# DaughterBoard.net
KiCad netlist of a schematic drawn in EAGLE
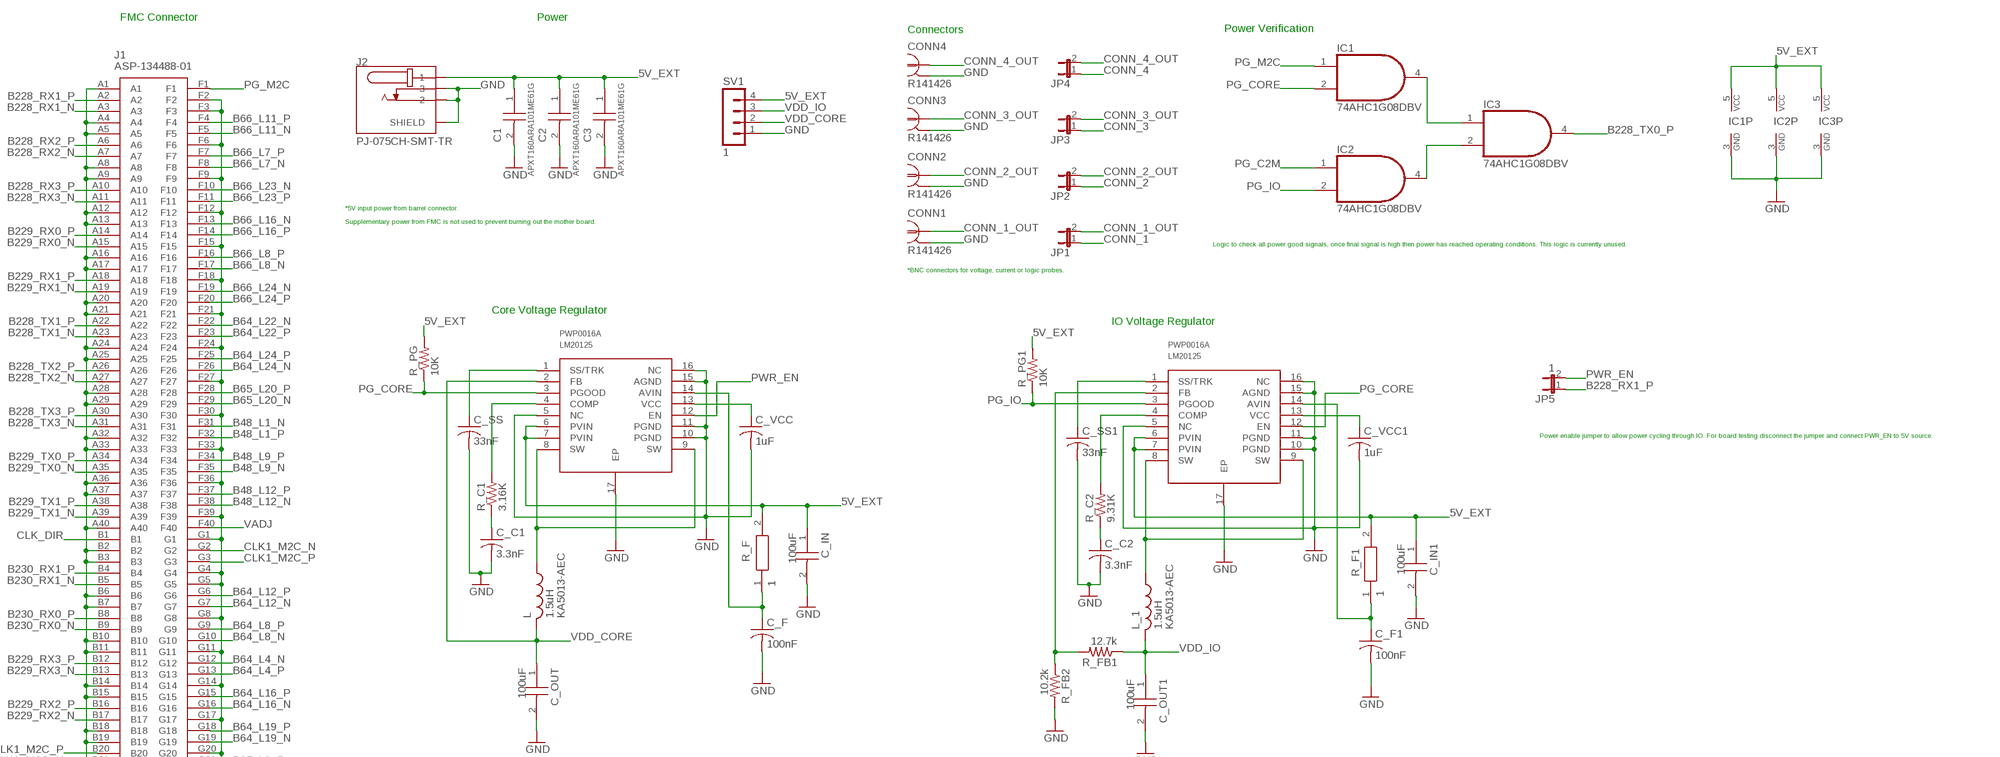
[diagram p0: schematic, sheet 1, part 1 of 3]
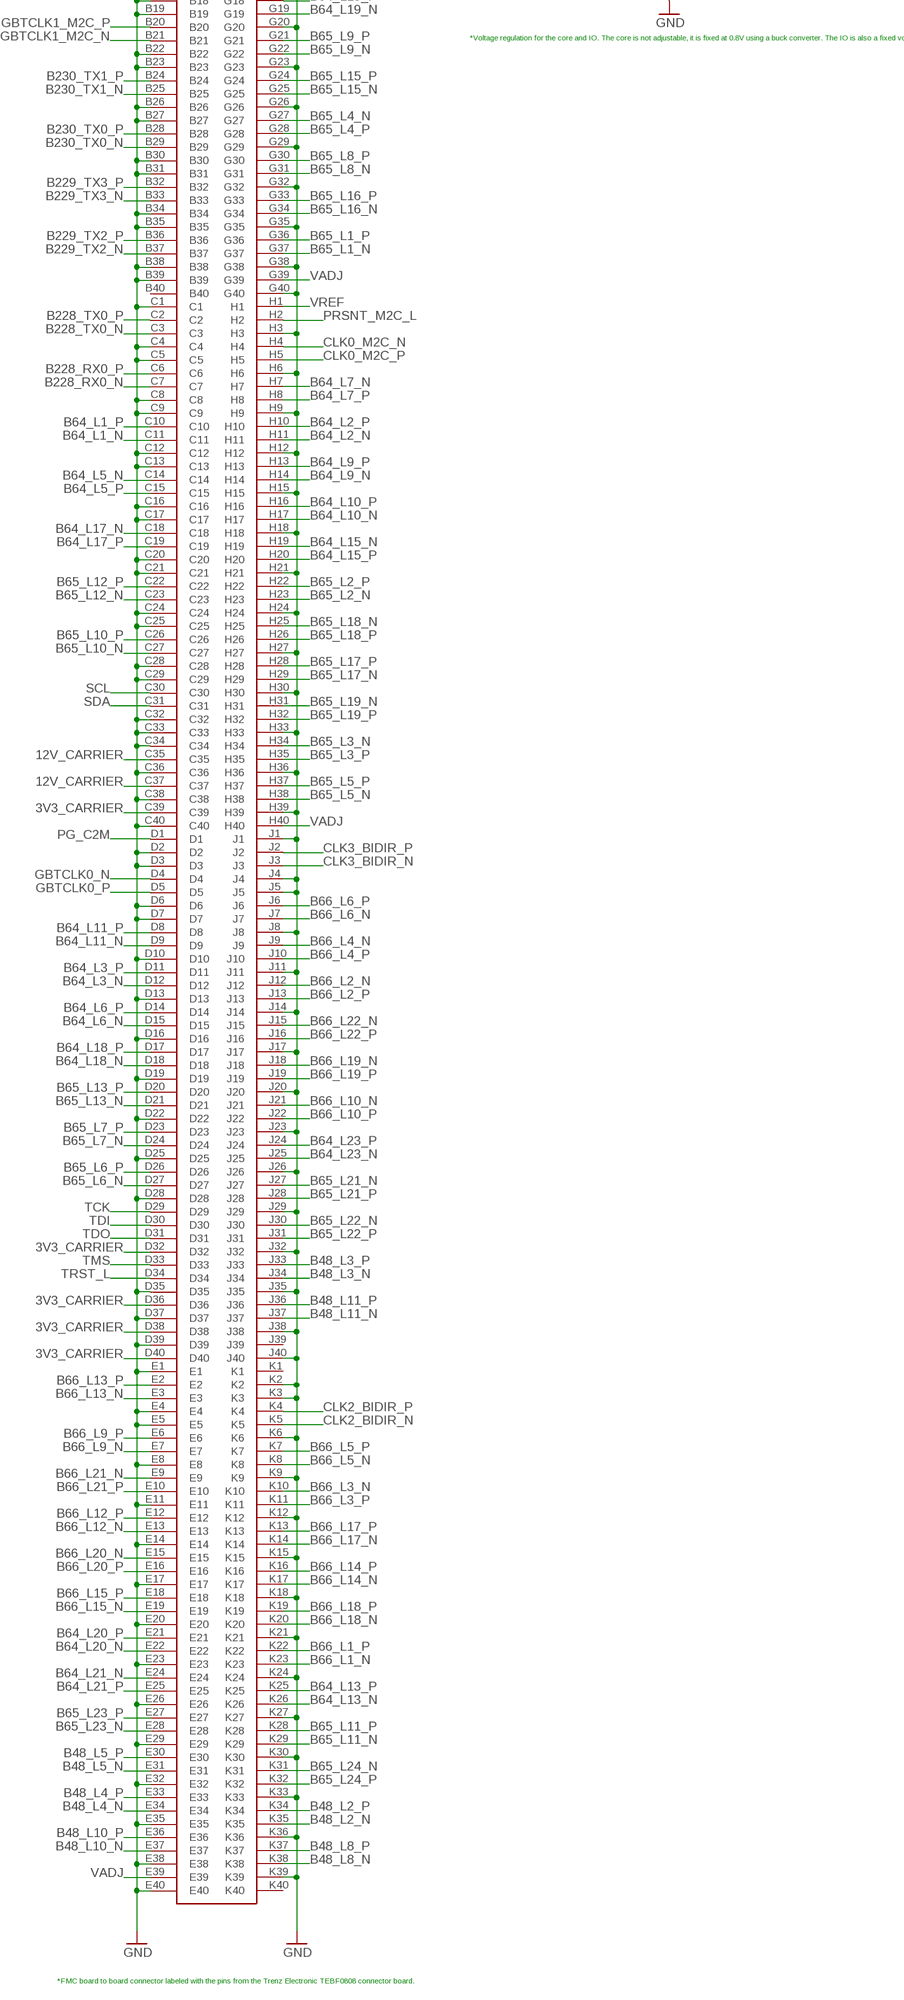
[diagram p1: schematic, sheet 1, part 2 of 3]
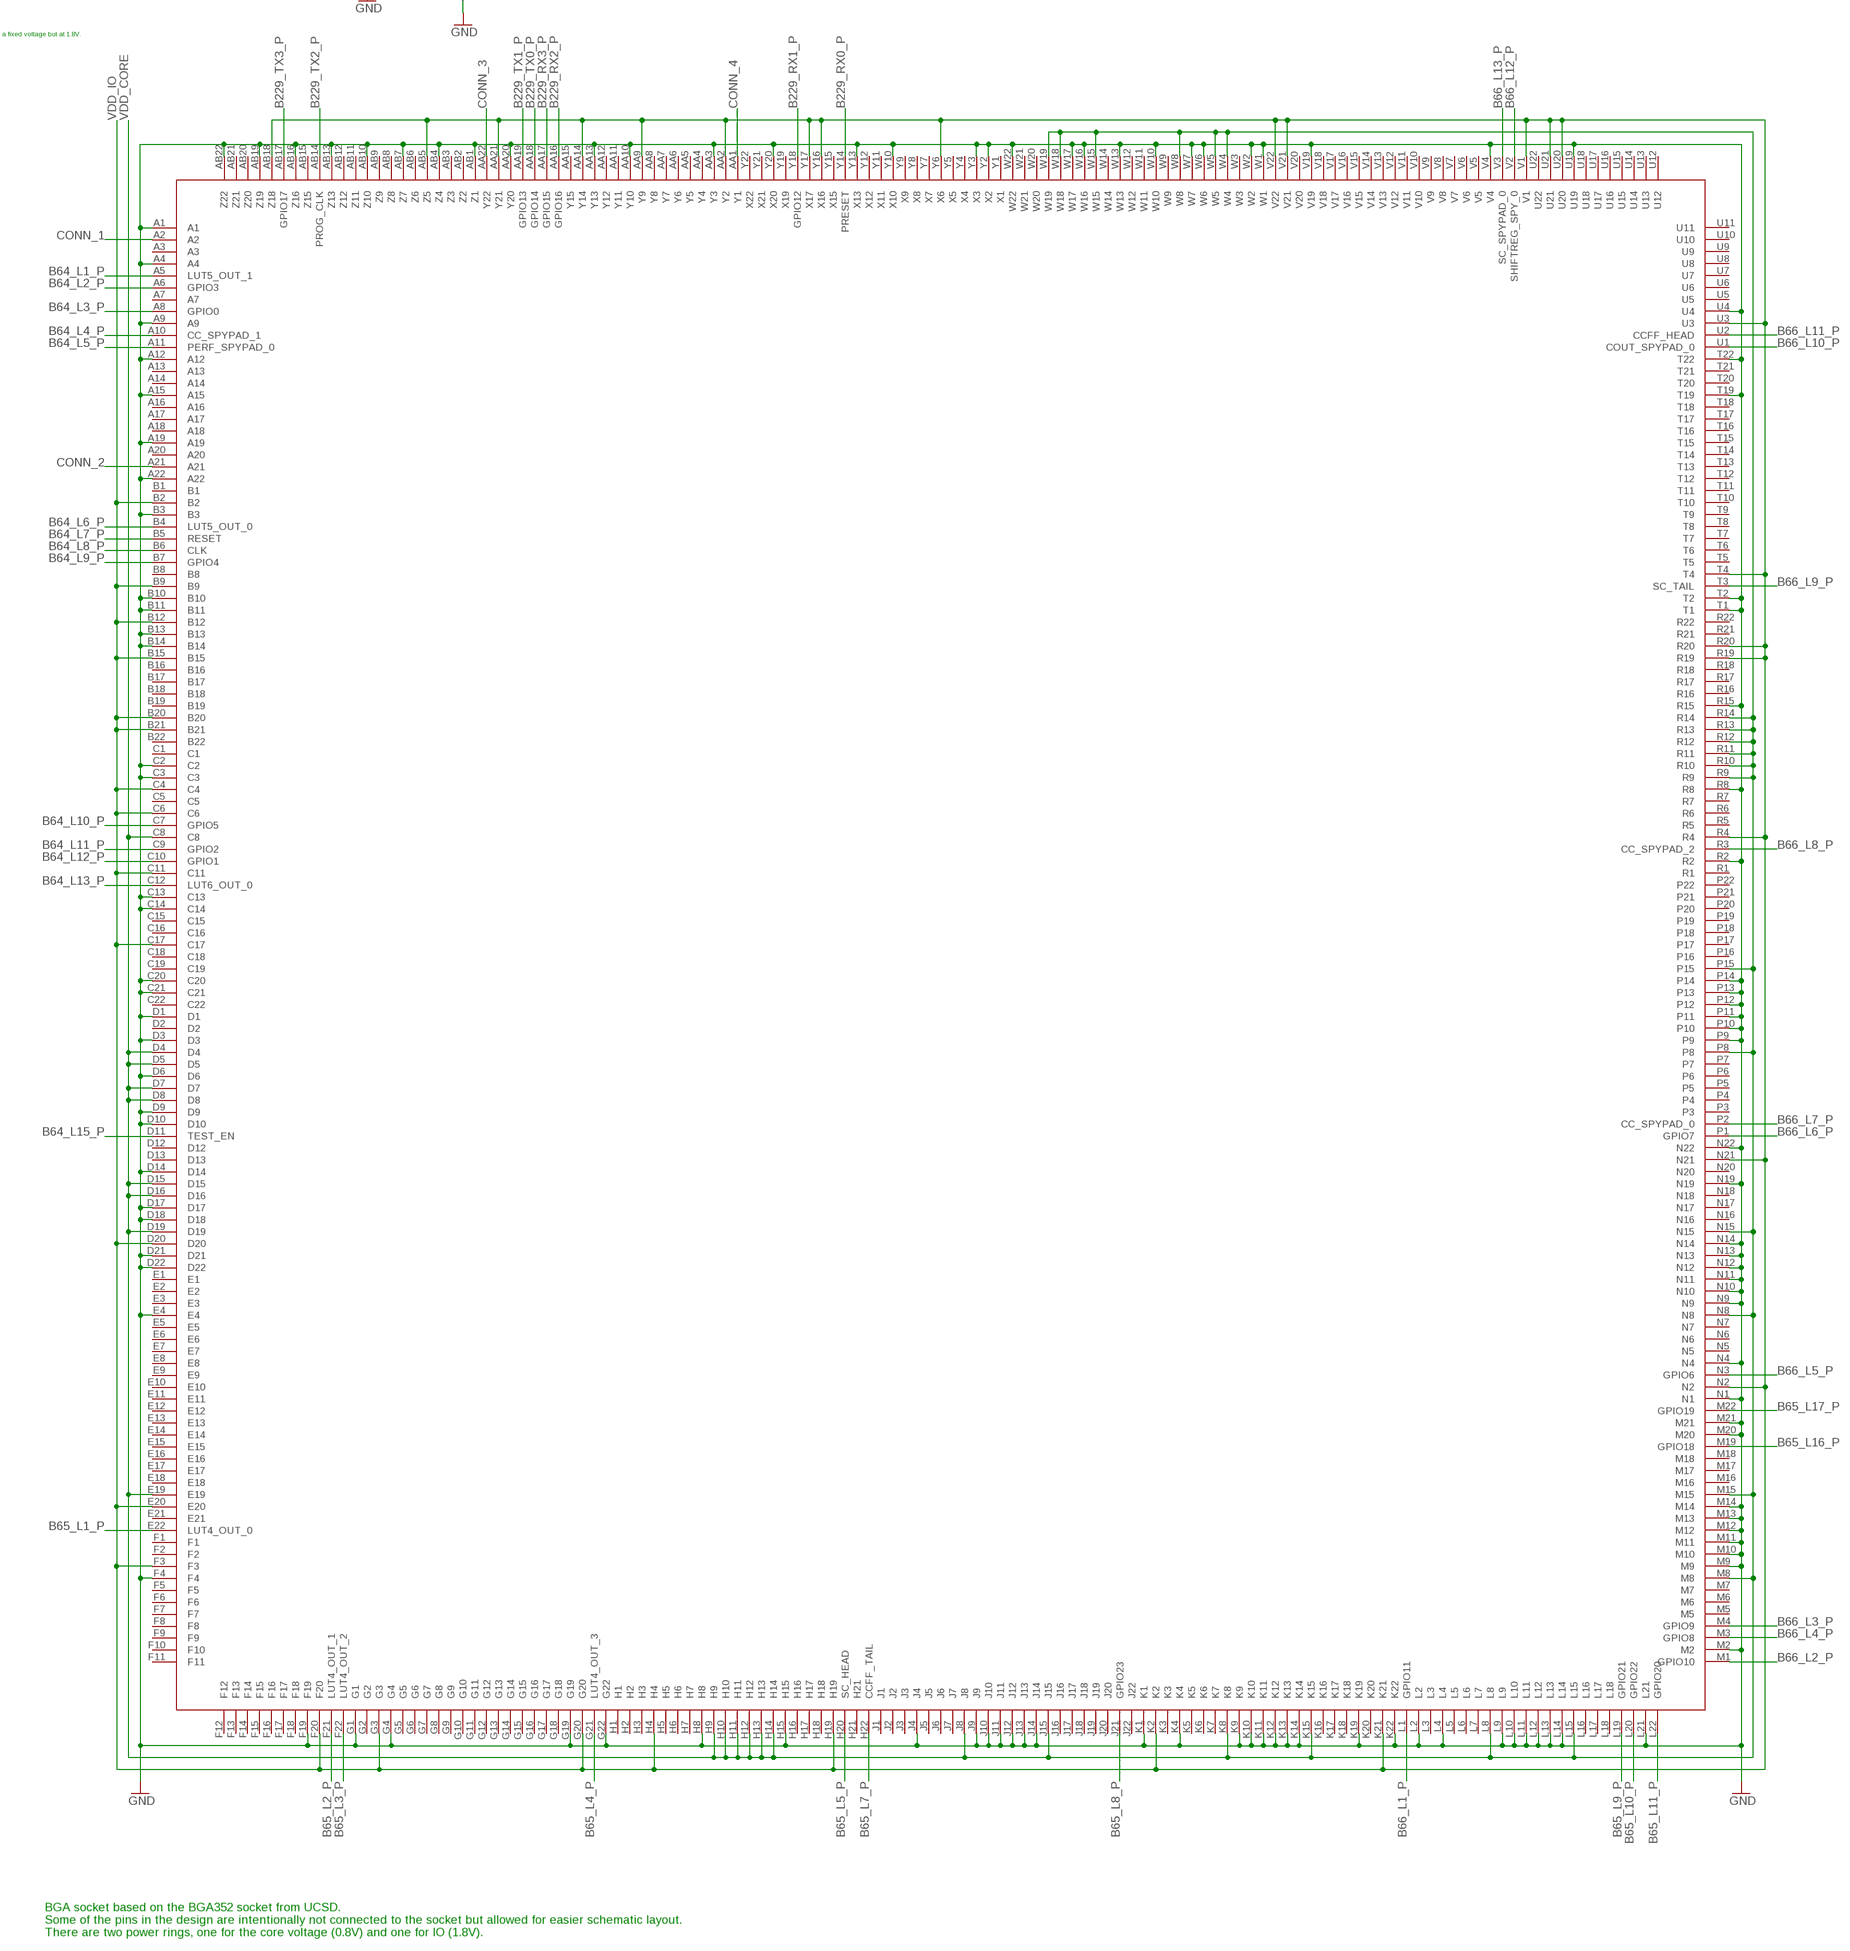
[diagram p2: schematic, sheet 1, part 3 of 3]

(export (version "E")
  (design (tool "Eeschema 10.0.6"))
  (components
    (comp (ref "C1")
      (value "APXT160ARA101ME61G")
      (footprint "eagle-import:CAPAE530X610N")
      (fields (field (name "MOUSER_PART_NUMBER") "661-APXT160A101ME61G"))
      (libsource (lib "eagle-import") (part "APXT160ARA101ME61G"))
    )
    (comp (ref "C2")
      (value "APXT160ARA101ME61G")
      (footprint "eagle-import:CAPAE530X610N")
      (fields (field (name "MOUSER_PART_NUMBER") "661-APXT160A101ME61G"))
      (libsource (lib "eagle-import") (part "APXT160ARA101ME61G"))
    )
    (comp (ref "C3")
      (value "APXT160ARA101ME61G")
      (footprint "eagle-import:CAPAE530X610N")
      (fields (field (name "MOUSER_PART_NUMBER") "661-APXT160A101ME61G"))
      (libsource (lib "eagle-import") (part "APXT160ARA101ME61G"))
    )
    (comp (ref "CONN1")
      (value "R141426")
      (footprint "eagle-import:R141426")
      (fields
        (field (name "MF") "FARNELL")
        (field (name "MPN") "R141426161")
        (field (name "SPICEPREFIX") "X")
      )
      (libsource (lib "eagle-import") (part "R141426"))
    )
    (comp (ref "CONN2")
      (value "R141426")
      (footprint "eagle-import:R141426")
      (fields (field (name "MF") "FARNELL") (field (name "MPN") "R141426161"))
      (libsource (lib "eagle-import") (part "R141426"))
    )
    (comp (ref "CONN3")
      (value "R141426")
      (footprint "eagle-import:R141426")
      (fields (field (name "MF") "FARNELL") (field (name "MPN") "R141426161"))
      (libsource (lib "eagle-import") (part "R141426"))
    )
    (comp (ref "CONN4")
      (value "R141426")
      (footprint "eagle-import:R141426")
      (fields (field (name "MF") "FARNELL") (field (name "MPN") "R141426161"))
      (libsource (lib "eagle-import") (part "R141426"))
    )
    (comp (ref "C_C1")
      (value "3.3nF")
      (footprint "eagle-import:C0805")
      (libsource (lib "eagle-import") (part "C-USC0805"))
    )
    (comp (ref "C_C2")
      (value "3.3nF")
      (footprint "eagle-import:C0805")
      (libsource (lib "eagle-import") (part "C-USC0805"))
    )
    (comp (ref "C_F")
      (value "100nF")
      (footprint "eagle-import:C0805")
      (libsource (lib "eagle-import") (part "C-USC0805"))
    )
    (comp (ref "C_F1")
      (value "100nF")
      (footprint "eagle-import:C0805")
      (libsource (lib "eagle-import") (part "C-USC0805"))
    )
    (comp (ref "C_IN")
      (value "100uF")
      (footprint "eagle-import:CAPC2012X145N")
      (fields
        (field (name "MANUFACTURER_PART_NUMBER") "GRM21BR60J107ME15L")
        (field (name "MOUSER_PART_NUMBER") "81-GRM21BR60J107ME5L")
      )
      (libsource (lib "eagle-import") (part "GRM21BR60J107ME15L"))
    )
    (comp (ref "C_IN1")
      (value "100uF")
      (footprint "eagle-import:CAPC2012X145N")
      (fields
        (field (name "MANUFACTURER_PART_NUMBER") "GRM21BR60J107ME15L")
        (field (name "MOUSER_PART_NUMBER") "81-GRM21BR60J107ME5L")
      )
      (libsource (lib "eagle-import") (part "GRM21BR60J107ME15L"))
    )
    (comp (ref "C_OUT")
      (value "100uF")
      (footprint "eagle-import:CAPC2012X145N")
      (fields
        (field (name "MANUFACTURER_PART_NUMBER") "GRM21BR60J107ME15L")
        (field (name "MOUSER_PART_NUMBER") "81-GRM21BR60J107ME5L")
      )
      (libsource (lib "eagle-import") (part "GRM21BR60J107ME15L"))
    )
    (comp (ref "C_OUT1")
      (value "100uF")
      (footprint "eagle-import:CAPC2012X145N")
      (fields
        (field (name "MANUFACTURER_PART_NUMBER") "GRM21BR60J107ME15L")
        (field (name "MOUSER_PART_NUMBER") "81-GRM21BR60J107ME5L")
      )
      (libsource (lib "eagle-import") (part "GRM21BR60J107ME15L"))
    )
    (comp (ref "C_SS")
      (value "33nF")
      (footprint "eagle-import:C0805")
      (libsource (lib "eagle-import") (part "C-USC0805"))
    )
    (comp (ref "C_SS1")
      (value "33nF")
      (footprint "eagle-import:C0805")
      (libsource (lib "eagle-import") (part "C-USC0805"))
    )
    (comp (ref "C_VCC")
      (value "1uF")
      (footprint "eagle-import:C0805")
      (libsource (lib "eagle-import") (part "C-USC0805"))
    )
    (comp (ref "C_VCC1")
      (value "1uF")
      (footprint "eagle-import:C0805")
      (libsource (lib "eagle-import") (part "C-USC0805"))
    )
    (comp (ref "IC1")
      (value "74AHC1G08DBV")
      (footprint "eagle-import:SOT23-5")
      (libsource (lib "eagle-import") (part "741G08DBVAHC"))
    )
    (comp (ref "IC2")
      (value "74AHC1G08DBV")
      (footprint "eagle-import:SOT23-5")
      (libsource (lib "eagle-import") (part "741G08DBVAHC"))
    )
    (comp (ref "IC3")
      (value "74AHC1G08DBV")
      (footprint "eagle-import:SOT23-5")
      (libsource (lib "eagle-import") (part "741G08DBVAHC"))
    )
    (comp (ref "J1")
      (value "ASP-134488-01")
      (footprint "eagle-import:ASP13448801")
      (fields (field (name "MOUSER_PART_NUMBER") "200-ASP-134488-01"))
      (libsource (lib "eagle-import") (part "ASP-134488-01"))
    )
    (comp (ref "J2")
      (value "PJ-075CH-SMT-TR")
      (footprint "eagle-import:CUI_PJ-075CH-SMT-TR")
      (fields (field (name "MANUFACTURER") "CUI"))
      (libsource (lib "eagle-import") (part "PJ-075CH-SMT-TR"))
    )
    (comp (ref "JP1")
      (value "JP1E")
      (footprint "eagle-import:JP1")
      (libsource (lib "eagle-import") (part "JP1E"))
    )
    (comp (ref "JP2")
      (value "JP1E")
      (footprint "eagle-import:JP1")
      (libsource (lib "eagle-import") (part "JP1E"))
    )
    (comp (ref "JP3")
      (value "JP1E")
      (footprint "eagle-import:JP1")
      (libsource (lib "eagle-import") (part "JP1E"))
    )
    (comp (ref "JP4")
      (value "JP1E")
      (footprint "eagle-import:JP1")
      (libsource (lib "eagle-import") (part "JP1E"))
    )
    (comp (ref "JP5")
      (value "1")
      (footprint "eagle-import:JP1")
      (libsource (lib "eagle-import") (part "JP1E"))
    )
    (comp (ref "L")
      (value "KA5013-AEC")
      (footprint "eagle-import:INDDFN400X400X180-2N")
      (libsource (lib "eagle-import") (part "KA5013-AEC"))
    )
    (comp (ref "L_1")
      (value "KA5013-AEC")
      (footprint "eagle-import:INDDFN400X400X180-2N")
      (libsource (lib "eagle-import") (part "KA5013-AEC"))
    )
    (comp (ref "R_C1")
      (value "3.16K")
      (footprint "eagle-import:R0805")
      (libsource (lib "eagle-import") (part "R-US_R0805"))
    )
    (comp (ref "R_C2")
      (value "9.31K")
      (footprint "eagle-import:R0805")
      (libsource (lib "eagle-import") (part "R-US_R0805"))
    )
    (comp (ref "R_F")
      (value "1")
      (footprint "eagle-import:RESC1608X55N")
      (fields
        (field (name "MANUFACTURER_PART_NUMBER") "RT0603BRD071RL")
        (field (name "MOUSER_PART_NUMBER") "603-RT0603BRD071RL")
      )
      (libsource (lib "eagle-import") (part "RT0603BRD071RL"))
    )
    (comp (ref "R_F1")
      (value "1")
      (footprint "eagle-import:RESC1608X55N")
      (fields
        (field (name "MANUFACTURER_PART_NUMBER") "RT0603BRD071RL")
        (field (name "MOUSER_PART_NUMBER") "603-RT0603BRD071RL")
      )
      (libsource (lib "eagle-import") (part "RT0603BRD071RL"))
    )
    (comp (ref "R_FB1")
      (value "12.7k")
      (footprint "eagle-import:R0805")
      (libsource (lib "eagle-import") (part "R-US_R0805"))
    )
    (comp (ref "R_FB2")
      (value "10.2k")
      (footprint "eagle-import:R0805")
      (libsource (lib "eagle-import") (part "R-US_R0805"))
    )
    (comp (ref "R_PG")
      (value "10K")
      (footprint "eagle-import:R0805")
      (libsource (lib "eagle-import") (part "R-US_R0805"))
    )
    (comp (ref "R_PG1")
      (value "10K")
      (footprint "eagle-import:R0805")
      (libsource (lib "eagle-import") (part "R-US_R0805"))
    )
    (comp (ref "SV1")
      (value "1")
      (footprint "eagle-import:MA04-1")
      (libsource (lib "eagle-import") (part "MA04-1"))
    )
    (comp (ref "U$1")
      (value "LM20125/LM20125Q")
      (footprint "eagle-import:SOP65P640X120-17T330L")
      (libsource (lib "eagle-import") (part "LM20125/LM20125Q"))
    )
    (comp (ref "U$2")
      (value "BGA352")
      (footprint "eagle-import:BGA484C100P22X22_2400X2400X220N")
      (libsource (lib "eagle-import") (part "BGA352"))
    )
    (comp (ref "U$3")
      (value "LM20125/LM20125Q")
      (footprint "eagle-import:SOP65P640X120-17T330L")
      (libsource (lib "eagle-import") (part "LM20125/LM20125Q"))
    )
  )
  (nets
    (net (code "1") (name "/3V3_CARRIER") (class "Default")
      (node (ref "J1") (pin "C39") (pinfunction "C39_C39") (pintype "bidirectional"))
      (node (ref "J1") (pin "D32") (pinfunction "D32_D32") (pintype "bidirectional"))
      (node (ref "J1") (pin "D36") (pinfunction "D36_D36") (pintype "bidirectional"))
      (node (ref "J1") (pin "D38") (pinfunction "D38_D38") (pintype "bidirectional"))
      (node (ref "J1") (pin "D40") (pinfunction "D40_D40") (pintype "bidirectional"))
    )
    (net (code "2") (name "/5V_EXT") (class "Default")
      (node (ref "C1") (pin "1") (pinfunction "+_1") (pintype "bidirectional"))
      (node (ref "C2") (pin "1") (pinfunction "+_1") (pintype "bidirectional"))
      (node (ref "C3") (pin "1") (pinfunction "+_1") (pintype "bidirectional"))
      (node (ref "C_IN") (pin "1") (pinfunction "1_1") (pintype "bidirectional"))
      (node (ref "C_IN1") (pin "1") (pinfunction "1_1") (pintype "bidirectional"))
      (node (ref "IC1") (pin "5") (pinfunction "VCC_5") (pintype "power_in"))
      (node (ref "IC2") (pin "5") (pinfunction "VCC_5") (pintype "power_in"))
      (node (ref "IC3") (pin "5") (pinfunction "VCC_5") (pintype "power_in"))
      (node (ref "J2") (pin "1") (pinfunction "1_1") (pintype "passive"))
      (node (ref "R_F") (pin "2") (pinfunction "2_2") (pintype "bidirectional"))
      (node (ref "R_F1") (pin "2") (pinfunction "2_2") (pintype "bidirectional"))
      (node (ref "R_PG") (pin "2") (pinfunction "2_2") (pintype "passive"))
      (node (ref "R_PG1") (pin "2") (pinfunction "2_2") (pintype "passive"))
      (node (ref "SV1") (pin "4") (pinfunction "4_4") (pintype "passive"))
      (node (ref "U$1") (pin "6") (pinfunction "PVIN_6") (pintype "bidirectional"))
      (node (ref "U$1") (pin "7") (pinfunction "PVIN_7") (pintype "bidirectional"))
      (node (ref "U$3") (pin "6") (pinfunction "PVIN_6") (pintype "bidirectional"))
      (node (ref "U$3") (pin "7") (pinfunction "PVIN_7") (pintype "bidirectional"))
    )
    (net (code "3") (name "/12V_CARRIER") (class "Default")
      (node (ref "J1") (pin "C35") (pinfunction "C35_C35") (pintype "bidirectional"))
      (node (ref "J1") (pin "C37") (pinfunction "C37_C37") (pintype "bidirectional"))
    )
    (net (code "4") (name "/B48_L1_N") (class "Default")
      (node (ref "J1") (pin "F31") (pinfunction "F31_F31") (pintype "bidirectional"))
    )
    (net (code "5") (name "/B48_L1_P") (class "Default")
      (node (ref "J1") (pin "F32") (pinfunction "F32_F32") (pintype "bidirectional"))
    )
    (net (code "6") (name "/B48_L2_N") (class "Default")
      (node (ref "J1") (pin "K35") (pinfunction "K35_K35") (pintype "bidirectional"))
    )
    (net (code "7") (name "/B48_L2_P") (class "Default")
      (node (ref "J1") (pin "K34") (pinfunction "K34_K34") (pintype "bidirectional"))
    )
    (net (code "8") (name "/B48_L3_N") (class "Default")
      (node (ref "J1") (pin "J34") (pinfunction "J34_J34") (pintype "bidirectional"))
    )
    (net (code "9") (name "/B48_L3_P") (class "Default")
      (node (ref "J1") (pin "J33") (pinfunction "J33_J33") (pintype "bidirectional"))
    )
    (net (code "10") (name "/B48_L4_N") (class "Default")
      (node (ref "J1") (pin "E34") (pinfunction "E34_E34") (pintype "bidirectional"))
    )
    (net (code "11") (name "/B48_L4_P") (class "Default")
      (node (ref "J1") (pin "E33") (pinfunction "E33_E33") (pintype "bidirectional"))
    )
    (net (code "12") (name "/B48_L5_N") (class "Default")
      (node (ref "J1") (pin "E31") (pinfunction "E31_E31") (pintype "bidirectional"))
    )
    (net (code "13") (name "/B48_L5_P") (class "Default")
      (node (ref "J1") (pin "E30") (pinfunction "E30_E30") (pintype "bidirectional"))
    )
    (net (code "14") (name "/B48_L8_N") (class "Default")
      (node (ref "J1") (pin "K38") (pinfunction "K38_K38") (pintype "bidirectional"))
    )
    (net (code "15") (name "/B48_L8_P") (class "Default")
      (node (ref "J1") (pin "K37") (pinfunction "K37_K37") (pintype "bidirectional"))
    )
    (net (code "16") (name "/B48_L9_N") (class "Default")
      (node (ref "J1") (pin "F35") (pinfunction "F35_F35") (pintype "bidirectional"))
    )
    (net (code "17") (name "/B48_L9_P") (class "Default")
      (node (ref "J1") (pin "F34") (pinfunction "F34_F34") (pintype "bidirectional"))
    )
    (net (code "18") (name "/B48_L10_N") (class "Default")
      (node (ref "J1") (pin "E37") (pinfunction "E37_E37") (pintype "bidirectional"))
    )
    (net (code "19") (name "/B48_L10_P") (class "Default")
      (node (ref "J1") (pin "E36") (pinfunction "E36_E36") (pintype "bidirectional"))
    )
    (net (code "20") (name "/B48_L11_N") (class "Default")
      (node (ref "J1") (pin "J37") (pinfunction "J37_J37") (pintype "bidirectional"))
    )
    (net (code "21") (name "/B48_L11_P") (class "Default")
      (node (ref "J1") (pin "J36") (pinfunction "J36_J36") (pintype "bidirectional"))
    )
    (net (code "22") (name "/B48_L12_N") (class "Default")
      (node (ref "J1") (pin "F38") (pinfunction "F38_F38") (pintype "bidirectional"))
    )
    (net (code "23") (name "/B48_L12_P") (class "Default")
      (node (ref "J1") (pin "F37") (pinfunction "F37_F37") (pintype "bidirectional"))
    )
    (net (code "24") (name "/B64_L1_N") (class "Default")
      (node (ref "J1") (pin "C11") (pinfunction "C11_C11") (pintype "bidirectional"))
    )
    (net (code "25") (name "/B64_L1_P") (class "Default")
      (node (ref "J1") (pin "C10") (pinfunction "C10_C10") (pintype "bidirectional"))
      (node (ref "U$2") (pin "A5") (pinfunction "LUT5_OUT_1_A5") (pintype "bidirectional"))
    )
    (net (code "26") (name "/B64_L2_N") (class "Default")
      (node (ref "J1") (pin "H11") (pinfunction "H11_H11") (pintype "bidirectional"))
    )
    (net (code "27") (name "/B64_L2_P") (class "Default")
      (node (ref "J1") (pin "H10") (pinfunction "H10_H10") (pintype "bidirectional"))
      (node (ref "U$2") (pin "A6") (pinfunction "GPIO3_A6") (pintype "bidirectional"))
    )
    (net (code "28") (name "/B64_L3_N") (class "Default")
      (node (ref "J1") (pin "D12") (pinfunction "D12_D12") (pintype "bidirectional"))
    )
    (net (code "29") (name "/B64_L3_P") (class "Default")
      (node (ref "J1") (pin "D11") (pinfunction "D11_D11") (pintype "bidirectional"))
      (node (ref "U$2") (pin "A8") (pinfunction "GPIO0_A8") (pintype "bidirectional"))
    )
    (net (code "30") (name "/B64_L4_N") (class "Default")
      (node (ref "J1") (pin "G12") (pinfunction "G12_G12") (pintype "bidirectional"))
    )
    (net (code "31") (name "/B64_L4_P") (class "Default")
      (node (ref "J1") (pin "G13") (pinfunction "G13_G13") (pintype "bidirectional"))
      (node (ref "U$2") (pin "A10") (pinfunction "CC_SPYPAD_1_A10") (pintype "bidirectional"))
    )
    (net (code "32") (name "/B64_L5_N") (class "Default")
      (node (ref "J1") (pin "C14") (pinfunction "C14_C14") (pintype "bidirectional"))
    )
    (net (code "33") (name "/B64_L5_P") (class "Default")
      (node (ref "J1") (pin "C15") (pinfunction "C15_C15") (pintype "bidirectional"))
      (node (ref "U$2") (pin "A11") (pinfunction "PERF_SPYPAD_0_A11") (pintype "bidirectional"))
    )
    (net (code "34") (name "/B64_L6_N") (class "Default")
      (node (ref "J1") (pin "D15") (pinfunction "D15_D15") (pintype "bidirectional"))
    )
    (net (code "35") (name "/B64_L6_P") (class "Default")
      (node (ref "J1") (pin "D14") (pinfunction "D14_D14") (pintype "bidirectional"))
      (node (ref "U$2") (pin "B4") (pinfunction "LUT5_OUT_0_B4") (pintype "bidirectional"))
    )
    (net (code "36") (name "/B64_L7_N") (class "Default")
      (node (ref "J1") (pin "H7") (pinfunction "H7_H7") (pintype "bidirectional"))
    )
    (net (code "37") (name "/B64_L7_P") (class "Default")
      (node (ref "J1") (pin "H8") (pinfunction "H8_H8") (pintype "bidirectional"))
      (node (ref "U$2") (pin "B5") (pinfunction "RESET_B5") (pintype "bidirectional"))
    )
    (net (code "38") (name "/B64_L8_N") (class "Default")
      (node (ref "J1") (pin "G10") (pinfunction "G10_G10") (pintype "bidirectional"))
    )
    (net (code "39") (name "/B64_L8_P") (class "Default")
      (node (ref "J1") (pin "G9") (pinfunction "G9_G9") (pintype "bidirectional"))
      (node (ref "U$2") (pin "B6") (pinfunction "CLK_B6") (pintype "bidirectional"))
    )
    (net (code "40") (name "/B64_L9_N") (class "Default")
      (node (ref "J1") (pin "H14") (pinfunction "H14_H14") (pintype "bidirectional"))
    )
    (net (code "41") (name "/B64_L9_P") (class "Default")
      (node (ref "J1") (pin "H13") (pinfunction "H13_H13") (pintype "bidirectional"))
      (node (ref "U$2") (pin "B7") (pinfunction "GPIO4_B7") (pintype "bidirectional"))
    )
    (net (code "42") (name "/B64_L10_N") (class "Default")
      (node (ref "J1") (pin "H17") (pinfunction "H17_H17") (pintype "bidirectional"))
    )
    (net (code "43") (name "/B64_L10_P") (class "Default")
      (node (ref "J1") (pin "H16") (pinfunction "H16_H16") (pintype "bidirectional"))
      (node (ref "U$2") (pin "C7") (pinfunction "GPIO5_C7") (pintype "bidirectional"))
    )
    (net (code "44") (name "/B64_L11_N") (class "Default")
      (node (ref "J1") (pin "D9") (pinfunction "D9_D9") (pintype "bidirectional"))
    )
    (net (code "45") (name "/B64_L11_P") (class "Default")
      (node (ref "J1") (pin "D8") (pinfunction "D8_D8") (pintype "bidirectional"))
      (node (ref "U$2") (pin "C9") (pinfunction "GPIO2_C9") (pintype "bidirectional"))
    )
    (net (code "46") (name "/B64_L12_N") (class "Default")
      (node (ref "J1") (pin "G7") (pinfunction "G7_G7") (pintype "bidirectional"))
    )
    (net (code "47") (name "/B64_L12_P") (class "Default")
      (node (ref "J1") (pin "G6") (pinfunction "G6_G6") (pintype "bidirectional"))
      (node (ref "U$2") (pin "C10") (pinfunction "GPIO1_C10") (pintype "bidirectional"))
    )
    (net (code "48") (name "/B64_L13_N") (class "Default")
      (node (ref "J1") (pin "K26") (pinfunction "K26_K26") (pintype "bidirectional"))
    )
    (net (code "49") (name "/B64_L13_P") (class "Default")
      (node (ref "J1") (pin "K25") (pinfunction "K25_K25") (pintype "bidirectional"))
      (node (ref "U$2") (pin "C12") (pinfunction "LUT6_OUT_0_C12") (pintype "bidirectional"))
    )
    (net (code "50") (name "/B64_L15_N") (class "Default")
      (node (ref "J1") (pin "H19") (pinfunction "H19_H19") (pintype "bidirectional"))
    )
    (net (code "51") (name "/B64_L15_P") (class "Default")
      (node (ref "J1") (pin "H20") (pinfunction "H20_H20") (pintype "bidirectional"))
      (node (ref "U$2") (pin "D11") (pinfunction "TEST_EN_D11") (pintype "bidirectional"))
    )
    (net (code "52") (name "/B64_L16_N") (class "Default")
      (node (ref "J1") (pin "G16") (pinfunction "G16_G16") (pintype "bidirectional"))
    )
    (net (code "53") (name "/B64_L16_P") (class "Default")
      (node (ref "J1") (pin "G15") (pinfunction "G15_G15") (pintype "bidirectional"))
    )
    (net (code "54") (name "/B64_L17_N") (class "Default")
      (node (ref "J1") (pin "C18") (pinfunction "C18_C18") (pintype "bidirectional"))
    )
    (net (code "55") (name "/B64_L17_P") (class "Default")
      (node (ref "J1") (pin "C19") (pinfunction "C19_C19") (pintype "bidirectional"))
    )
    (net (code "56") (name "/B64_L18_N") (class "Default")
      (node (ref "J1") (pin "D18") (pinfunction "D18_D18") (pintype "bidirectional"))
    )
    (net (code "57") (name "/B64_L18_P") (class "Default")
      (node (ref "J1") (pin "D17") (pinfunction "D17_D17") (pintype "bidirectional"))
    )
    (net (code "58") (name "/B64_L19_N") (class "Default")
      (node (ref "J1") (pin "G19") (pinfunction "G19_G19") (pintype "bidirectional"))
    )
    (net (code "59") (name "/B64_L19_P") (class "Default")
      (node (ref "J1") (pin "G18") (pinfunction "G18_G18") (pintype "bidirectional"))
    )
    (net (code "60") (name "/B64_L20_N") (class "Default")
      (node (ref "J1") (pin "E22") (pinfunction "E22_E22") (pintype "bidirectional"))
    )
    (net (code "61") (name "/B64_L20_P") (class "Default")
      (node (ref "J1") (pin "E21") (pinfunction "E21_E21") (pintype "bidirectional"))
    )
    (net (code "62") (name "/B64_L21_N") (class "Default")
      (node (ref "J1") (pin "E24") (pinfunction "E24_E24") (pintype "bidirectional"))
    )
    (net (code "63") (name "/B64_L21_P") (class "Default")
      (node (ref "J1") (pin "E25") (pinfunction "E25_E25") (pintype "bidirectional"))
    )
    (net (code "64") (name "/B64_L22_N") (class "Default")
      (node (ref "J1") (pin "F22") (pinfunction "F22_F22") (pintype "bidirectional"))
    )
    (net (code "65") (name "/B64_L22_P") (class "Default")
      (node (ref "J1") (pin "F23") (pinfunction "F23_F23") (pintype "bidirectional"))
    )
    (net (code "66") (name "/B64_L23_N") (class "Default")
      (node (ref "J1") (pin "J25") (pinfunction "J25_J25") (pintype "bidirectional"))
    )
    (net (code "67") (name "/B64_L23_P") (class "Default")
      (node (ref "J1") (pin "J24") (pinfunction "J24_J24") (pintype "bidirectional"))
    )
    (net (code "68") (name "/B64_L24_N") (class "Default")
      (node (ref "J1") (pin "F26") (pinfunction "F26_F26") (pintype "bidirectional"))
    )
    (net (code "69") (name "/B64_L24_P") (class "Default")
      (node (ref "J1") (pin "F25") (pinfunction "F25_F25") (pintype "bidirectional"))
    )
    (net (code "70") (name "/B65_L1_N") (class "Default")
      (node (ref "J1") (pin "G37") (pinfunction "G37_G37") (pintype "bidirectional"))
    )
    (net (code "71") (name "/B65_L1_P") (class "Default")
      (node (ref "J1") (pin "G36") (pinfunction "G36_G36") (pintype "bidirectional"))
      (node (ref "U$2") (pin "E22") (pinfunction "LUT4_OUT_0_E22") (pintype "bidirectional"))
    )
    (net (code "72") (name "/B65_L2_N") (class "Default")
      (node (ref "J1") (pin "H23") (pinfunction "H23_H23") (pintype "bidirectional"))
    )
    (net (code "73") (name "/B65_L2_P") (class "Default")
      (node (ref "J1") (pin "H22") (pinfunction "H22_H22") (pintype "bidirectional"))
      (node (ref "U$2") (pin "F21") (pinfunction "LUT4_OUT_1_F21") (pintype "bidirectional"))
    )
    (net (code "74") (name "/B65_L3_N") (class "Default")
      (node (ref "J1") (pin "H34") (pinfunction "H34_H34") (pintype "bidirectional"))
    )
    (net (code "75") (name "/B65_L3_P") (class "Default")
      (node (ref "J1") (pin "H35") (pinfunction "H35_H35") (pintype "bidirectional"))
      (node (ref "U$2") (pin "F22") (pinfunction "LUT4_OUT_2_F22") (pintype "bidirectional"))
    )
    (net (code "76") (name "/B65_L4_N") (class "Default")
      (node (ref "J1") (pin "G27") (pinfunction "G27_G27") (pintype "bidirectional"))
    )
    (net (code "77") (name "/B65_L4_P") (class "Default")
      (node (ref "J1") (pin "G28") (pinfunction "G28_G28") (pintype "bidirectional"))
      (node (ref "U$2") (pin "G21") (pinfunction "LUT4_OUT_3_G21") (pintype "bidirectional"))
    )
    (net (code "78") (name "/B65_L5_N") (class "Default")
      (node (ref "J1") (pin "H38") (pinfunction "H38_H38") (pintype "bidirectional"))
    )
    (net (code "79") (name "/B65_L5_P") (class "Default")
      (node (ref "J1") (pin "H37") (pinfunction "H37_H37") (pintype "bidirectional"))
      (node (ref "U$2") (pin "H20") (pinfunction "SC_HEAD_H20") (pintype "bidirectional"))
    )
    (net (code "80") (name "/B65_L6_N") (class "Default")
      (node (ref "J1") (pin "D27") (pinfunction "D27_D27") (pintype "bidirectional"))
    )
    (net (code "81") (name "/B65_L6_P") (class "Default")
      (node (ref "J1") (pin "D26") (pinfunction "D26_D26") (pintype "bidirectional"))
    )
    (net (code "82") (name "/B65_L7_N") (class "Default")
      (node (ref "J1") (pin "D24") (pinfunction "D24_D24") (pintype "bidirectional"))
    )
    (net (code "83") (name "/B65_L7_P") (class "Default")
      (node (ref "J1") (pin "D23") (pinfunction "D23_D23") (pintype "bidirectional"))
      (node (ref "U$2") (pin "H22") (pinfunction "CCFF_TAIL_H22") (pintype "bidirectional"))
    )
    (net (code "84") (name "/B65_L8_N") (class "Default")
      (node (ref "J1") (pin "G31") (pinfunction "G31_G31") (pintype "bidirectional"))
    )
    (net (code "85") (name "/B65_L8_P") (class "Default")
      (node (ref "J1") (pin "G30") (pinfunction "G30_G30") (pintype "bidirectional"))
      (node (ref "U$2") (pin "J21") (pinfunction "GPIO23_J21") (pintype "bidirectional"))
    )
    (net (code "86") (name "/B65_L9_N") (class "Default")
      (node (ref "J1") (pin "G22") (pinfunction "G22_G22") (pintype "bidirectional"))
    )
    (net (code "87") (name "/B65_L9_P") (class "Default")
      (node (ref "J1") (pin "G21") (pinfunction "G21_G21") (pintype "bidirectional"))
      (node (ref "U$2") (pin "L19") (pinfunction "GPIO21_L19") (pintype "bidirectional"))
    )
    (net (code "88") (name "/B65_L10_N") (class "Default")
      (node (ref "J1") (pin "C27") (pinfunction "C27_C27") (pintype "bidirectional"))
    )
    (net (code "89") (name "/B65_L10_P") (class "Default")
      (node (ref "J1") (pin "C26") (pinfunction "C26_C26") (pintype "bidirectional"))
      (node (ref "U$2") (pin "L20") (pinfunction "GPIO22_L20") (pintype "bidirectional"))
    )
    (net (code "90") (name "/B65_L11_N") (class "Default")
      (node (ref "J1") (pin "K29") (pinfunction "K29_K29") (pintype "bidirectional"))
    )
    (net (code "91") (name "/B65_L11_P") (class "Default")
      (node (ref "J1") (pin "K28") (pinfunction "K28_K28") (pintype "bidirectional"))
      (node (ref "U$2") (pin "L22") (pinfunction "GPIO20_L22") (pintype "bidirectional"))
    )
    (net (code "92") (name "/B65_L12_N") (class "Default")
      (node (ref "J1") (pin "C23") (pinfunction "C23_C23") (pintype "bidirectional"))
    )
    (net (code "93") (name "/B65_L12_P") (class "Default")
      (node (ref "J1") (pin "C22") (pinfunction "C22_C22") (pintype "bidirectional"))
    )
    (net (code "94") (name "/B65_L13_N") (class "Default")
      (node (ref "J1") (pin "D21") (pinfunction "D21_D21") (pintype "bidirectional"))
    )
    (net (code "95") (name "/B65_L13_P") (class "Default")
      (node (ref "J1") (pin "D20") (pinfunction "D20_D20") (pintype "bidirectional"))
    )
    (net (code "96") (name "/B65_L15_N") (class "Default")
      (node (ref "J1") (pin "G25") (pinfunction "G25_G25") (pintype "bidirectional"))
    )
    (net (code "97") (name "/B65_L15_P") (class "Default")
      (node (ref "J1") (pin "G24") (pinfunction "G24_G24") (pintype "bidirectional"))
    )
    (net (code "98") (name "/B65_L16_N") (class "Default")
      (node (ref "J1") (pin "G34") (pinfunction "G34_G34") (pintype "bidirectional"))
    )
    (net (code "99") (name "/B65_L16_P") (class "Default")
      (node (ref "J1") (pin "G33") (pinfunction "G33_G33") (pintype "bidirectional"))
      (node (ref "U$2") (pin "M19") (pinfunction "GPIO18_M19") (pintype "bidirectional"))
    )
    (net (code "100") (name "/B65_L17_N") (class "Default")
      (node (ref "J1") (pin "H29") (pinfunction "H29_H29") (pintype "bidirectional"))
    )
    (net (code "101") (name "/B65_L17_P") (class "Default")
      (node (ref "J1") (pin "H28") (pinfunction "H28_H28") (pintype "bidirectional"))
      (node (ref "U$2") (pin "M22") (pinfunction "GPIO19_M22") (pintype "bidirectional"))
    )
    (net (code "102") (name "/B65_L18_N") (class "Default")
      (node (ref "J1") (pin "H25") (pinfunction "H25_H25") (pintype "bidirectional"))
    )
    (net (code "103") (name "/B65_L18_P") (class "Default")
      (node (ref "J1") (pin "H26") (pinfunction "H26_H26") (pintype "bidirectional"))
    )
    (net (code "104") (name "/B65_L19_N") (class "Default")
      (node (ref "J1") (pin "H31") (pinfunction "H31_H31") (pintype "bidirectional"))
    )
    (net (code "105") (name "/B65_L19_P") (class "Default")
      (node (ref "J1") (pin "H32") (pinfunction "H32_H32") (pintype "bidirectional"))
    )
    (net (code "106") (name "/B65_L20_N") (class "Default")
      (node (ref "J1") (pin "F29") (pinfunction "F29_F29") (pintype "bidirectional"))
    )
    (net (code "107") (name "/B65_L20_P") (class "Default")
      (node (ref "J1") (pin "F28") (pinfunction "F28_F28") (pintype "bidirectional"))
    )
    (net (code "108") (name "/B65_L21_N") (class "Default")
      (node (ref "J1") (pin "J27") (pinfunction "J27_J27") (pintype "bidirectional"))
    )
    (net (code "109") (name "/B65_L21_P") (class "Default")
      (node (ref "J1") (pin "J28") (pinfunction "J28_J28") (pintype "bidirectional"))
    )
    (net (code "110") (name "/B65_L22_N") (class "Default")
      (node (ref "J1") (pin "J30") (pinfunction "J30_J30") (pintype "bidirectional"))
    )
    (net (code "111") (name "/B65_L22_P") (class "Default")
      (node (ref "J1") (pin "J31") (pinfunction "J31_J31") (pintype "bidirectional"))
    )
    (net (code "112") (name "/B65_L23_N") (class "Default")
      (node (ref "J1") (pin "E28") (pinfunction "E28_E28") (pintype "bidirectional"))
    )
    (net (code "113") (name "/B65_L23_P") (class "Default")
      (node (ref "J1") (pin "E27") (pinfunction "E27_E27") (pintype "bidirectional"))
    )
    (net (code "114") (name "/B65_L24_N") (class "Default")
      (node (ref "J1") (pin "K31") (pinfunction "K31_K31") (pintype "bidirectional"))
    )
    (net (code "115") (name "/B65_L24_P") (class "Default")
      (node (ref "J1") (pin "K32") (pinfunction "K32_K32") (pintype "bidirectional"))
    )
    (net (code "116") (name "/B66_L1_N") (class "Default")
      (node (ref "J1") (pin "K23") (pinfunction "K23_K23") (pintype "bidirectional"))
    )
    (net (code "117") (name "/B66_L1_P") (class "Default")
      (node (ref "J1") (pin "K22") (pinfunction "K22_K22") (pintype "bidirectional"))
      (node (ref "U$2") (pin "L1") (pinfunction "GPIO11_L1") (pintype "bidirectional"))
    )
    (net (code "118") (name "/B66_L2_N") (class "Default")
      (node (ref "J1") (pin "J12") (pinfunction "J12_J12") (pintype "bidirectional"))
    )
    (net (code "119") (name "/B66_L2_P") (class "Default")
      (node (ref "J1") (pin "J13") (pinfunction "J13_J13") (pintype "bidirectional"))
      (node (ref "U$2") (pin "M1") (pinfunction "GPIO10_M1") (pintype "bidirectional"))
    )
    (net (code "120") (name "/B66_L3_N") (class "Default")
      (node (ref "J1") (pin "K10") (pinfunction "K10_K10") (pintype "bidirectional"))
    )
    (net (code "121") (name "/B66_L3_P") (class "Default")
      (node (ref "J1") (pin "K11") (pinfunction "K11_K11") (pintype "bidirectional"))
      (node (ref "U$2") (pin "M4") (pinfunction "GPIO9_M4") (pintype "bidirectional"))
    )
    (net (code "122") (name "/B66_L4_N") (class "Default")
      (node (ref "J1") (pin "J9") (pinfunction "J9_J9") (pintype "bidirectional"))
    )
    (net (code "123") (name "/B66_L4_P") (class "Default")
      (node (ref "J1") (pin "J10") (pinfunction "J10_J10") (pintype "bidirectional"))
      (node (ref "U$2") (pin "M3") (pinfunction "GPIO8_M3") (pintype "bidirectional"))
    )
    (net (code "124") (name "/B66_L5_N") (class "Default")
      (node (ref "J1") (pin "K8") (pinfunction "K8_K8") (pintype "bidirectional"))
    )
    (net (code "125") (name "/B66_L5_P") (class "Default")
      (node (ref "J1") (pin "K7") (pinfunction "K7_K7") (pintype "bidirectional"))
      (node (ref "U$2") (pin "N3") (pinfunction "GPIO6_N3") (pintype "bidirectional"))
    )
    (net (code "126") (name "/B66_L6_N") (class "Default")
      (node (ref "J1") (pin "J7") (pinfunction "J7_J7") (pintype "bidirectional"))
    )
    (net (code "127") (name "/B66_L6_P") (class "Default")
      (node (ref "J1") (pin "J6") (pinfunction "J6_J6") (pintype "bidirectional"))
      (node (ref "U$2") (pin "P1") (pinfunction "GPIO7_P1") (pintype "bidirectional"))
    )
    (net (code "128") (name "/B66_L7_N") (class "Default")
      (node (ref "J1") (pin "F8") (pinfunction "F8_F8") (pintype "bidirectional"))
    )
    (net (code "129") (name "/B66_L7_P") (class "Default")
      (node (ref "J1") (pin "F7") (pinfunction "F7_F7") (pintype "bidirectional"))
      (node (ref "U$2") (pin "P2") (pinfunction "CC_SPYPAD_0_P2") (pintype "bidirectional"))
    )
    (net (code "130") (name "/B66_L8_N") (class "Default")
      (node (ref "J1") (pin "F17") (pinfunction "F17_F17") (pintype "bidirectional"))
    )
    (net (code "131") (name "/B66_L8_P") (class "Default")
      (node (ref "J1") (pin "F16") (pinfunction "F16_F16") (pintype "bidirectional"))
      (node (ref "U$2") (pin "R3") (pinfunction "CC_SPYPAD_2_R3") (pintype "bidirectional"))
    )
    (net (code "132") (name "/B66_L9_N") (class "Default")
      (node (ref "J1") (pin "E7") (pinfunction "E7_E7") (pintype "bidirectional"))
    )
    (net (code "133") (name "/B66_L9_P") (class "Default")
      (node (ref "J1") (pin "E6") (pinfunction "E6_E6") (pintype "bidirectional"))
      (node (ref "U$2") (pin "T3") (pinfunction "SC_TAIL_T3") (pintype "bidirectional"))
    )
    (net (code "134") (name "/B66_L10_N") (class "Default")
      (node (ref "J1") (pin "J21") (pinfunction "J21_J21") (pintype "bidirectional"))
    )
    (net (code "135") (name "/B66_L10_P") (class "Default")
      (node (ref "J1") (pin "J22") (pinfunction "J22_J22") (pintype "bidirectional"))
      (node (ref "U$2") (pin "U1") (pinfunction "COUT_SPYPAD_0_U1") (pintype "bidirectional"))
    )
    (net (code "136") (name "/B66_L11_N") (class "Default")
      (node (ref "J1") (pin "F5") (pinfunction "F5_F5") (pintype "bidirectional"))
    )
    (net (code "137") (name "/B66_L11_P") (class "Default")
      (node (ref "J1") (pin "F4") (pinfunction "F4_F4") (pintype "bidirectional"))
      (node (ref "U$2") (pin "U2") (pinfunction "CCFF_HEAD_U2") (pintype "bidirectional"))
    )
    (net (code "138") (name "/B66_L12_N") (class "Default")
      (node (ref "J1") (pin "E13") (pinfunction "E13_E13") (pintype "bidirectional"))
    )
    (net (code "139") (name "/B66_L12_P") (class "Default")
      (node (ref "J1") (pin "E12") (pinfunction "E12_E12") (pintype "bidirectional"))
      (node (ref "U$2") (pin "V2") (pinfunction "SHIFTREG_SPY_0_V2") (pintype "bidirectional"))
    )
    (net (code "140") (name "/B66_L13_N") (class "Default")
      (node (ref "J1") (pin "E3") (pinfunction "E3_E3") (pintype "bidirectional"))
    )
    (net (code "141") (name "/B66_L13_P") (class "Default")
      (node (ref "J1") (pin "E2") (pinfunction "E2_E2") (pintype "bidirectional"))
      (node (ref "U$2") (pin "V3") (pinfunction "SC_SPYPAD_0_V3") (pintype "bidirectional"))
    )
    (net (code "142") (name "/B66_L14_N") (class "Default")
      (node (ref "J1") (pin "K17") (pinfunction "K17_K17") (pintype "bidirectional"))
    )
    (net (code "143") (name "/B66_L14_P") (class "Default")
      (node (ref "J1") (pin "K16") (pinfunction "K16_K16") (pintype "bidirectional"))
    )
    (net (code "144") (name "/B66_L15_N") (class "Default")
      (node (ref "J1") (pin "E19") (pinfunction "E19_E19") (pintype "bidirectional"))
    )
    (net (code "145") (name "/B66_L15_P") (class "Default")
      (node (ref "J1") (pin "E18") (pinfunction "E18_E18") (pintype "bidirectional"))
    )
    (net (code "146") (name "/B66_L16_N") (class "Default")
      (node (ref "J1") (pin "F13") (pinfunction "F13_F13") (pintype "bidirectional"))
    )
    (net (code "147") (name "/B66_L16_P") (class "Default")
      (node (ref "J1") (pin "F14") (pinfunction "F14_F14") (pintype "bidirectional"))
    )
    (net (code "148") (name "/B66_L17_N") (class "Default")
      (node (ref "J1") (pin "K14") (pinfunction "K14_K14") (pintype "bidirectional"))
    )
    (net (code "149") (name "/B66_L17_P") (class "Default")
      (node (ref "J1") (pin "K13") (pinfunction "K13_K13") (pintype "bidirectional"))
    )
    (net (code "150") (name "/B66_L18_N") (class "Default")
      (node (ref "J1") (pin "K20") (pinfunction "K20_K20") (pintype "bidirectional"))
    )
    (net (code "151") (name "/B66_L18_P") (class "Default")
      (node (ref "J1") (pin "K19") (pinfunction "K19_K19") (pintype "bidirectional"))
    )
    (net (code "152") (name "/B66_L19_N") (class "Default")
      (node (ref "J1") (pin "J18") (pinfunction "J18_J18") (pintype "bidirectional"))
    )
    (net (code "153") (name "/B66_L19_P") (class "Default")
      (node (ref "J1") (pin "J19") (pinfunction "J19_J19") (pintype "bidirectional"))
    )
    (net (code "154") (name "/B66_L20_N") (class "Default")
      (node (ref "J1") (pin "E15") (pinfunction "E15_E15") (pintype "bidirectional"))
    )
    (net (code "155") (name "/B66_L20_P") (class "Default")
      (node (ref "J1") (pin "E16") (pinfunction "E16_E16") (pintype "bidirectional"))
    )
    (net (code "156") (name "/B66_L21_N") (class "Default")
      (node (ref "J1") (pin "E9") (pinfunction "E9_E9") (pintype "bidirectional"))
    )
    (net (code "157") (name "/B66_L21_P") (class "Default")
      (node (ref "J1") (pin "E10") (pinfunction "E10_E10") (pintype "bidirectional"))
    )
    (net (code "158") (name "/B66_L22_N") (class "Default")
      (node (ref "J1") (pin "J15") (pinfunction "J15_J15") (pintype "bidirectional"))
    )
    (net (code "159") (name "/B66_L22_P") (class "Default")
      (node (ref "J1") (pin "J16") (pinfunction "J16_J16") (pintype "bidirectional"))
    )
    (net (code "160") (name "/B66_L23_N") (class "Default")
      (node (ref "J1") (pin "F10") (pinfunction "F10_F10") (pintype "bidirectional"))
    )
    (net (code "161") (name "/B66_L23_P") (class "Default")
      (node (ref "J1") (pin "F11") (pinfunction "F11_F11") (pintype "bidirectional"))
    )
    (net (code "162") (name "/B66_L24_N") (class "Default")
      (node (ref "J1") (pin "F19") (pinfunction "F19_F19") (pintype "bidirectional"))
    )
    (net (code "163") (name "/B66_L24_P") (class "Default")
      (node (ref "J1") (pin "F20") (pinfunction "F20_F20") (pintype "bidirectional"))
    )
    (net (code "164") (name "/B228_RX0_N") (class "Default")
      (node (ref "J1") (pin "C7") (pinfunction "C7_C7") (pintype "bidirectional"))
    )
    (net (code "165") (name "/B228_RX0_P") (class "Default")
      (node (ref "J1") (pin "C6") (pinfunction "C6_C6") (pintype "bidirectional"))
    )
    (net (code "166") (name "/B228_RX1_N") (class "Default")
      (node (ref "J1") (pin "A3") (pinfunction "A3_A3") (pintype "bidirectional"))
    )
    (net (code "167") (name "/B228_RX1_P") (class "Default")
      (node (ref "J1") (pin "A2") (pinfunction "A2_A2") (pintype "bidirectional"))
      (node (ref "JP5") (pin "1") (pinfunction "1_1") (pintype "passive"))
    )
    (net (code "168") (name "/B228_RX2_N") (class "Default")
      (node (ref "J1") (pin "A7") (pinfunction "A7_A7") (pintype "bidirectional"))
    )
    (net (code "169") (name "/B228_RX2_P") (class "Default")
      (node (ref "J1") (pin "A6") (pinfunction "A6_A6") (pintype "bidirectional"))
    )
    (net (code "170") (name "/B228_RX3_N") (class "Default")
      (node (ref "J1") (pin "A11") (pinfunction "A11_A11") (pintype "bidirectional"))
    )
    (net (code "171") (name "/B228_RX3_P") (class "Default")
      (node (ref "J1") (pin "A10") (pinfunction "A10_A10") (pintype "bidirectional"))
    )
    (net (code "172") (name "/B228_TX0_N") (class "Default")
      (node (ref "J1") (pin "C3") (pinfunction "C3_C3") (pintype "bidirectional"))
    )
    (net (code "173") (name "/B228_TX0_P") (class "Default")
      (node (ref "IC3") (pin "4") (pinfunction "O_4") (pintype "output"))
      (node (ref "J1") (pin "C2") (pinfunction "C2_C2") (pintype "bidirectional"))
    )
    (net (code "174") (name "/B228_TX1_N") (class "Default")
      (node (ref "J1") (pin "A23") (pinfunction "A23_A23") (pintype "bidirectional"))
    )
    (net (code "175") (name "/B228_TX1_P") (class "Default")
      (node (ref "J1") (pin "A22") (pinfunction "A22_A22") (pintype "bidirectional"))
    )
    (net (code "176") (name "/B228_TX2_N") (class "Default")
      (node (ref "J1") (pin "A27") (pinfunction "A27_A27") (pintype "bidirectional"))
    )
    (net (code "177") (name "/B228_TX2_P") (class "Default")
      (node (ref "J1") (pin "A26") (pinfunction "A26_A26") (pintype "bidirectional"))
    )
    (net (code "178") (name "/B228_TX3_N") (class "Default")
      (node (ref "J1") (pin "A31") (pinfunction "A31_A31") (pintype "bidirectional"))
    )
    (net (code "179") (name "/B228_TX3_P") (class "Default")
      (node (ref "J1") (pin "A30") (pinfunction "A30_A30") (pintype "bidirectional"))
    )
    (net (code "180") (name "/B229_RX0_N") (class "Default")
      (node (ref "J1") (pin "A15") (pinfunction "A15_A15") (pintype "bidirectional"))
    )
    (net (code "181") (name "/B229_RX0_P") (class "Default")
      (node (ref "J1") (pin "A14") (pinfunction "A14_A14") (pintype "bidirectional"))
      (node (ref "U$2") (pin "Y14") (pinfunction "PRESET_Y14") (pintype "bidirectional"))
    )
    (net (code "182") (name "/B229_RX1_N") (class "Default")
      (node (ref "J1") (pin "A19") (pinfunction "A19_A19") (pintype "bidirectional"))
    )
    (net (code "183") (name "/B229_RX1_P") (class "Default")
      (node (ref "J1") (pin "A18") (pinfunction "A18_A18") (pintype "bidirectional"))
      (node (ref "U$2") (pin "Y18") (pinfunction "GPIO12_Y18") (pintype "bidirectional"))
    )
    (net (code "184") (name "/B229_RX2_N") (class "Default")
      (node (ref "J1") (pin "B17") (pinfunction "B17_B17") (pintype "bidirectional"))
    )
    (net (code "185") (name "/B229_RX2_P") (class "Default")
      (node (ref "J1") (pin "B16") (pinfunction "B16_B16") (pintype "bidirectional"))
      (node (ref "U$2") (pin "AA16") (pinfunction "GPIO16_AA16") (pintype "bidirectional"))
    )
    (net (code "186") (name "/B229_RX3_N") (class "Default")
      (node (ref "J1") (pin "B13") (pinfunction "B13_B13") (pintype "bidirectional"))
    )
    (net (code "187") (name "/B229_RX3_P") (class "Default")
      (node (ref "J1") (pin "B12") (pinfunction "B12_B12") (pintype "bidirectional"))
      (node (ref "U$2") (pin "AA17") (pinfunction "GPIO15_AA17") (pintype "bidirectional"))
    )
    (net (code "188") (name "/B229_TX0_N") (class "Default")
      (node (ref "J1") (pin "A35") (pinfunction "A35_A35") (pintype "bidirectional"))
    )
    (net (code "189") (name "/B229_TX0_P") (class "Default")
      (node (ref "J1") (pin "A34") (pinfunction "A34_A34") (pintype "bidirectional"))
      (node (ref "U$2") (pin "AA18") (pinfunction "GPIO14_AA18") (pintype "bidirectional"))
    )
    (net (code "190") (name "/B229_TX1_N") (class "Default")
      (node (ref "J1") (pin "A39") (pinfunction "A39_A39") (pintype "bidirectional"))
    )
    (net (code "191") (name "/B229_TX1_P") (class "Default")
      (node (ref "J1") (pin "A38") (pinfunction "A38_A38") (pintype "bidirectional"))
      (node (ref "U$2") (pin "AA19") (pinfunction "GPIO13_AA19") (pintype "bidirectional"))
    )
    (net (code "192") (name "/B229_TX2_N") (class "Default")
      (node (ref "J1") (pin "B37") (pinfunction "B37_B37") (pintype "bidirectional"))
    )
    (net (code "193") (name "/B229_TX2_P") (class "Default")
      (node (ref "J1") (pin "B36") (pinfunction "B36_B36") (pintype "bidirectional"))
      (node (ref "U$2") (pin "AB14") (pinfunction "PROG_CLK_AB14") (pintype "bidirectional"))
    )
    (net (code "194") (name "/B229_TX3_N") (class "Default")
      (node (ref "J1") (pin "B33") (pinfunction "B33_B33") (pintype "bidirectional"))
    )
    (net (code "195") (name "/B229_TX3_P") (class "Default")
      (node (ref "J1") (pin "B32") (pinfunction "B32_B32") (pintype "bidirectional"))
      (node (ref "U$2") (pin "AB17") (pinfunction "GPIO17_AB17") (pintype "bidirectional"))
    )
    (net (code "196") (name "/B230_RX0_N") (class "Default")
      (node (ref "J1") (pin "B9") (pinfunction "B9_B9") (pintype "bidirectional"))
    )
    (net (code "197") (name "/B230_RX0_P") (class "Default")
      (node (ref "J1") (pin "B8") (pinfunction "B8_B8") (pintype "bidirectional"))
    )
    (net (code "198") (name "/B230_RX1_N") (class "Default")
      (node (ref "J1") (pin "B5") (pinfunction "B5_B5") (pintype "bidirectional"))
    )
    (net (code "199") (name "/B230_RX1_P") (class "Default")
      (node (ref "J1") (pin "B4") (pinfunction "B4_B4") (pintype "bidirectional"))
    )
    (net (code "200") (name "/B230_TX0_N") (class "Default")
      (node (ref "J1") (pin "B29") (pinfunction "B29_B29") (pintype "bidirectional"))
    )
    (net (code "201") (name "/B230_TX0_P") (class "Default")
      (node (ref "J1") (pin "B28") (pinfunction "B28_B28") (pintype "bidirectional"))
    )
    (net (code "202") (name "/B230_TX1_N") (class "Default")
      (node (ref "J1") (pin "B25") (pinfunction "B25_B25") (pintype "bidirectional"))
    )
    (net (code "203") (name "/B230_TX1_P") (class "Default")
      (node (ref "J1") (pin "B24") (pinfunction "B24_B24") (pintype "bidirectional"))
    )
    (net (code "204") (name "/CLK0_M2C_N") (class "Default")
      (node (ref "J1") (pin "H4") (pinfunction "H4_H4") (pintype "bidirectional"))
    )
    (net (code "205") (name "/CLK0_M2C_P") (class "Default")
      (node (ref "J1") (pin "H5") (pinfunction "H5_H5") (pintype "bidirectional"))
    )
    (net (code "206") (name "/CLK1_M2C_N") (class "Default")
      (node (ref "J1") (pin "G2") (pinfunction "G2_G2") (pintype "bidirectional"))
    )
    (net (code "207") (name "/CLK1_M2C_P") (class "Default")
      (node (ref "J1") (pin "G3") (pinfunction "G3_G3") (pintype "bidirectional"))
    )
    (net (code "208") (name "/CLK2_BIDIR_N") (class "Default")
      (node (ref "J1") (pin "K5") (pinfunction "K5_K5") (pintype "bidirectional"))
    )
    (net (code "209") (name "/CLK2_BIDIR_P") (class "Default")
      (node (ref "J1") (pin "K4") (pinfunction "K4_K4") (pintype "bidirectional"))
    )
    (net (code "210") (name "/CLK3_BIDIR_N") (class "Default")
      (node (ref "J1") (pin "J3") (pinfunction "J3_J3") (pintype "bidirectional"))
    )
    (net (code "211") (name "/CLK3_BIDIR_P") (class "Default")
      (node (ref "J1") (pin "J2") (pinfunction "J2_J2") (pintype "bidirectional"))
    )
    (net (code "212") (name "/CLK_DIR") (class "Default")
      (node (ref "J1") (pin "B1") (pinfunction "B1_B1") (pintype "bidirectional"))
    )
    (net (code "213") (name "/CONN_1") (class "Default")
      (node (ref "JP1") (pin "1") (pinfunction "1_1") (pintype "passive"))
      (node (ref "U$2") (pin "A2") (pinfunction "A2_A2") (pintype "bidirectional"))
    )
    (net (code "214") (name "/CONN_1_OUT") (class "Default")
      (node (ref "CONN1") (pin "1") (pinfunction "1_1") (pintype "passive"))
      (node (ref "JP1") (pin "2") (pinfunction "2_2") (pintype "passive"))
    )
    (net (code "215") (name "/CONN_2") (class "Default")
      (node (ref "JP2") (pin "1") (pinfunction "1_1") (pintype "passive"))
      (node (ref "U$2") (pin "A21") (pinfunction "A21_A21") (pintype "bidirectional"))
    )
    (net (code "216") (name "/CONN_2_OUT") (class "Default")
      (node (ref "CONN2") (pin "1") (pinfunction "1_1") (pintype "passive"))
      (node (ref "JP2") (pin "2") (pinfunction "2_2") (pintype "passive"))
    )
    (net (code "217") (name "/CONN_3") (class "Default")
      (node (ref "JP3") (pin "1") (pinfunction "1_1") (pintype "passive"))
      (node (ref "U$2") (pin "AA22") (pinfunction "Y22_AA22") (pintype "bidirectional"))
    )
    (net (code "218") (name "/CONN_3_OUT") (class "Default")
      (node (ref "CONN3") (pin "1") (pinfunction "1_1") (pintype "passive"))
      (node (ref "JP3") (pin "2") (pinfunction "2_2") (pintype "passive"))
    )
    (net (code "219") (name "/CONN_4") (class "Default")
      (node (ref "JP4") (pin "1") (pinfunction "1_1") (pintype "passive"))
      (node (ref "U$2") (pin "AA1") (pinfunction "Y1_AA1") (pintype "bidirectional"))
    )
    (net (code "220") (name "/CONN_4_OUT") (class "Default")
      (node (ref "CONN4") (pin "1") (pinfunction "1_1") (pintype "passive"))
      (node (ref "JP4") (pin "2") (pinfunction "2_2") (pintype "passive"))
    )
    (net (code "221") (name "/GBTCLK0_N") (class "Default")
      (node (ref "J1") (pin "D4") (pinfunction "D4_D4") (pintype "bidirectional"))
    )
    (net (code "222") (name "/GBTCLK0_P") (class "Default")
      (node (ref "J1") (pin "D5") (pinfunction "D5_D5") (pintype "bidirectional"))
    )
    (net (code "223") (name "/GBTCLK1_M2C_N") (class "Default")
      (node (ref "J1") (pin "B21") (pinfunction "B21_B21") (pintype "bidirectional"))
    )
    (net (code "224") (name "/GBTCLK1_M2C_P") (class "Default")
      (node (ref "J1") (pin "B20") (pinfunction "B20_B20") (pintype "bidirectional"))
    )
    (net (code "225") (name "/PG_C2M") (class "Default")
      (node (ref "IC2") (pin "1") (pinfunction "I0_1") (pintype "input"))
      (node (ref "J1") (pin "D1") (pinfunction "D1_D1") (pintype "bidirectional"))
    )
    (net (code "226") (name "/PG_CORE") (class "Default")
      (node (ref "IC1") (pin "2") (pinfunction "I1_2") (pintype "input"))
      (node (ref "R_PG") (pin "1") (pinfunction "1_1") (pintype "passive"))
      (node (ref "U$1") (pin "3") (pinfunction "PGOOD_3") (pintype "bidirectional"))
      (node (ref "U$3") (pin "12") (pinfunction "EN_12") (pintype "bidirectional"))
    )
    (net (code "227") (name "/PG_IO") (class "Default")
      (node (ref "IC2") (pin "2") (pinfunction "I1_2") (pintype "input"))
      (node (ref "R_PG1") (pin "1") (pinfunction "1_1") (pintype "passive"))
      (node (ref "U$3") (pin "3") (pinfunction "PGOOD_3") (pintype "bidirectional"))
    )
    (net (code "228") (name "/PG_M2C") (class "Default")
      (node (ref "IC1") (pin "1") (pinfunction "I0_1") (pintype "input"))
      (node (ref "J1") (pin "F1") (pinfunction "F1_F1") (pintype "bidirectional"))
    )
    (net (code "229") (name "/PRSNT_M2C_L") (class "Default")
      (node (ref "J1") (pin "H2") (pinfunction "H2_H2") (pintype "bidirectional"))
    )
    (net (code "230") (name "/PWR_EN") (class "Default")
      (node (ref "JP5") (pin "2") (pinfunction "2_2") (pintype "passive"))
      (node (ref "U$1") (pin "12") (pinfunction "EN_12") (pintype "bidirectional"))
    )
    (net (code "231") (name "/SCL") (class "Default")
      (node (ref "J1") (pin "C30") (pinfunction "C30_C30") (pintype "bidirectional"))
    )
    (net (code "232") (name "/SDA") (class "Default")
      (node (ref "J1") (pin "C31") (pinfunction "C31_C31") (pintype "bidirectional"))
    )
    (net (code "233") (name "/TCK") (class "Default")
      (node (ref "J1") (pin "D29") (pinfunction "D29_D29") (pintype "bidirectional"))
    )
    (net (code "234") (name "/TDI") (class "Default")
      (node (ref "J1") (pin "D30") (pinfunction "D30_D30") (pintype "bidirectional"))
    )
    (net (code "235") (name "/TDO") (class "Default")
      (node (ref "J1") (pin "D31") (pinfunction "D31_D31") (pintype "bidirectional"))
    )
    (net (code "236") (name "/TMS") (class "Default")
      (node (ref "J1") (pin "D33") (pinfunction "D33_D33") (pintype "bidirectional"))
    )
    (net (code "237") (name "/TRST_L") (class "Default")
      (node (ref "J1") (pin "D34") (pinfunction "D34_D34") (pintype "bidirectional"))
    )
    (net (code "238") (name "/VADJ") (class "Default")
      (node (ref "J1") (pin "E39") (pinfunction "E39_E39") (pintype "bidirectional"))
      (node (ref "J1") (pin "F40") (pinfunction "F40_F40") (pintype "bidirectional"))
      (node (ref "J1") (pin "G39") (pinfunction "G39_G39") (pintype "bidirectional"))
      (node (ref "J1") (pin "H40") (pinfunction "H40_H40") (pintype "bidirectional"))
    )
    (net (code "239") (name "/VDD_CORE") (class "Default")
      (node (ref "C_OUT") (pin "1") (pinfunction "1_1") (pintype "bidirectional"))
      (node (ref "L") (pin "2") (pinfunction "2_2") (pintype "passive"))
      (node (ref "SV1") (pin "2") (pinfunction "2_2") (pintype "passive"))
      (node (ref "U$1") (pin "2") (pinfunction "FB_2") (pintype "bidirectional"))
      (node (ref "U$2") (pin "C8") (pinfunction "C8_C8") (pintype "bidirectional"))
      (node (ref "U$2") (pin "D15") (pinfunction "D15_D15") (pintype "bidirectional"))
      (node (ref "U$2") (pin "D16") (pinfunction "D16_D16") (pintype "bidirectional"))
      (node (ref "U$2") (pin "D19") (pinfunction "D19_D19") (pintype "bidirectional"))
      (node (ref "U$2") (pin "D4") (pinfunction "D4_D4") (pintype "bidirectional"))
      (node (ref "U$2") (pin "D5") (pinfunction "D5_D5") (pintype "bidirectional"))
      (node (ref "U$2") (pin "D7") (pinfunction "D7_D7") (pintype "bidirectional"))
      (node (ref "U$2") (pin "D8") (pinfunction "D8_D8") (pintype "bidirectional"))
      (node (ref "U$2") (pin "E19") (pinfunction "E19_E19") (pintype "bidirectional"))
      (node (ref "U$2") (pin "H10") (pinfunction "H10_H10") (pintype "bidirectional"))
      (node (ref "U$2") (pin "H11") (pinfunction "H11_H11") (pintype "bidirectional"))
      (node (ref "U$2") (pin "H12") (pinfunction "H12_H12") (pintype "bidirectional"))
      (node (ref "U$2") (pin "H13") (pinfunction "H13_H13") (pintype "bidirectional"))
      (node (ref "U$2") (pin "H14") (pinfunction "H14_H14") (pintype "bidirectional"))
      (node (ref "U$2") (pin "H9") (pinfunction "H9_H9") (pintype "bidirectional"))
      (node (ref "U$2") (pin "J15") (pinfunction "J15_J15") (pintype "bidirectional"))
      (node (ref "U$2") (pin "J8") (pinfunction "J8_J8") (pintype "bidirectional"))
      (node (ref "U$2") (pin "K15") (pinfunction "K15_K15") (pintype "bidirectional"))
      (node (ref "U$2") (pin "K8") (pinfunction "K8_K8") (pintype "bidirectional"))
      (node (ref "U$2") (pin "L15") (pinfunction "L15_L15") (pintype "bidirectional"))
      (node (ref "U$2") (pin "L8") (pinfunction "L8_L8") (pintype "bidirectional"))
      (node (ref "U$2") (pin "M15") (pinfunction "M15_M15") (pintype "bidirectional"))
      (node (ref "U$2") (pin "M8") (pinfunction "M8_M8") (pintype "bidirectional"))
      (node (ref "U$2") (pin "N15") (pinfunction "N15_N15") (pintype "bidirectional"))
      (node (ref "U$2") (pin "N8") (pinfunction "N8_N8") (pintype "bidirectional"))
      (node (ref "U$2") (pin "P15") (pinfunction "P15_P15") (pintype "bidirectional"))
      (node (ref "U$2") (pin "P8") (pinfunction "P8_P8") (pintype "bidirectional"))
      (node (ref "U$2") (pin "R10") (pinfunction "R10_R10") (pintype "bidirectional"))
      (node (ref "U$2") (pin "R11") (pinfunction "R11_R11") (pintype "bidirectional"))
      (node (ref "U$2") (pin "R12") (pinfunction "R12_R12") (pintype "bidirectional"))
      (node (ref "U$2") (pin "R13") (pinfunction "R13_R13") (pintype "bidirectional"))
      (node (ref "U$2") (pin "R14") (pinfunction "R14_R14") (pintype "bidirectional"))
      (node (ref "U$2") (pin "R9") (pinfunction "R9_R9") (pintype "bidirectional"))
      (node (ref "U$2") (pin "W15") (pinfunction "W15_W15") (pintype "bidirectional"))
      (node (ref "U$2") (pin "W18") (pinfunction "W18_W18") (pintype "bidirectional"))
      (node (ref "U$2") (pin "W19") (pinfunction "W19_W19") (pintype "bidirectional"))
      (node (ref "U$2") (pin "W4") (pinfunction "W4_W4") (pintype "bidirectional"))
      (node (ref "U$2") (pin "W5") (pinfunction "W5_W5") (pintype "bidirectional"))
      (node (ref "U$2") (pin "W8") (pinfunction "W8_W8") (pintype "bidirectional"))
    )
    (net (code "240") (name "/VDD_IO") (class "Default")
      (node (ref "C_OUT1") (pin "1") (pinfunction "1_1") (pintype "bidirectional"))
      (node (ref "L_1") (pin "2") (pinfunction "2_2") (pintype "passive"))
      (node (ref "R_FB1") (pin "1") (pinfunction "1_1") (pintype "passive"))
      (node (ref "SV1") (pin "3") (pinfunction "3_3") (pintype "passive"))
      (node (ref "U$2") (pin "AA14") (pinfunction "Y14_AA14") (pintype "bidirectional"))
      (node (ref "U$2") (pin "AA2") (pinfunction "Y2_AA2") (pintype "bidirectional"))
      (node (ref "U$2") (pin "AA21") (pinfunction "Y21_AA21") (pintype "bidirectional"))
      (node (ref "U$2") (pin "AA9") (pinfunction "Y9_AA9") (pintype "bidirectional"))
      (node (ref "U$2") (pin "AB18") (pinfunction "Z18_AB18") (pintype "bidirectional"))
      (node (ref "U$2") (pin "AB5") (pinfunction "Z5_AB5") (pintype "bidirectional"))
      (node (ref "U$2") (pin "B12") (pinfunction "B12_B12") (pintype "bidirectional"))
      (node (ref "U$2") (pin "B15") (pinfunction "B15_B15") (pintype "bidirectional"))
      (node (ref "U$2") (pin "B2") (pinfunction "B2_B2") (pintype "bidirectional"))
      (node (ref "U$2") (pin "B20") (pinfunction "B20_B20") (pintype "bidirectional"))
      (node (ref "U$2") (pin "B21") (pinfunction "B21_B21") (pintype "bidirectional"))
      (node (ref "U$2") (pin "B9") (pinfunction "B9_B9") (pintype "bidirectional"))
      (node (ref "U$2") (pin "C11") (pinfunction "C11_C11") (pintype "bidirectional"))
      (node (ref "U$2") (pin "C17") (pinfunction "C17_C17") (pintype "bidirectional"))
      (node (ref "U$2") (pin "C4") (pinfunction "C4_C4") (pintype "bidirectional"))
      (node (ref "U$2") (pin "C6") (pinfunction "C6_C6") (pintype "bidirectional"))
      (node (ref "U$2") (pin "D20") (pinfunction "D20_D20") (pintype "bidirectional"))
      (node (ref "U$2") (pin "E20") (pinfunction "E20_E20") (pintype "bidirectional"))
      (node (ref "U$2") (pin "F20") (pinfunction "F20_F20") (pintype "bidirectional"))
      (node (ref "U$2") (pin "F3") (pinfunction "F3_F3") (pintype "bidirectional"))
      (node (ref "U$2") (pin "G20") (pinfunction "G20_G20") (pintype "bidirectional"))
      (node (ref "U$2") (pin "G3") (pinfunction "G3_G3") (pintype "bidirectional"))
      (node (ref "U$2") (pin "H19") (pinfunction "H19_H19") (pintype "bidirectional"))
      (node (ref "U$2") (pin "H4") (pinfunction "H4_H4") (pintype "bidirectional"))
      (node (ref "U$2") (pin "K2") (pinfunction "K2_K2") (pintype "bidirectional"))
      (node (ref "U$2") (pin "K21") (pinfunction "K21_K21") (pintype "bidirectional"))
      (node (ref "U$2") (pin "N2") (pinfunction "N2_N2") (pintype "bidirectional"))
      (node (ref "U$2") (pin "N21") (pinfunction "N21_N21") (pintype "bidirectional"))
      (node (ref "U$2") (pin "R19") (pinfunction "R19_R19") (pintype "bidirectional"))
      (node (ref "U$2") (pin "R20") (pinfunction "R20_R20") (pintype "bidirectional"))
      (node (ref "U$2") (pin "R4") (pinfunction "R4_R4") (pintype "bidirectional"))
      (node (ref "U$2") (pin "T4") (pinfunction "T4_T4") (pintype "bidirectional"))
      (node (ref "U$2") (pin "U20") (pinfunction "U20_U20") (pintype "bidirectional"))
      (node (ref "U$2") (pin "U21") (pinfunction "U21_U21") (pintype "bidirectional"))
      (node (ref "U$2") (pin "U3") (pinfunction "U3_U3") (pintype "bidirectional"))
      (node (ref "U$2") (pin "V1") (pinfunction "V1_V1") (pintype "bidirectional"))
      (node (ref "U$2") (pin "V21") (pinfunction "V21_V21") (pintype "bidirectional"))
      (node (ref "U$2") (pin "V22") (pinfunction "V22_V22") (pintype "bidirectional"))
      (node (ref "U$2") (pin "Y16") (pinfunction "X16_Y16") (pintype "bidirectional"))
      (node (ref "U$2") (pin "Y17") (pinfunction "X17_Y17") (pintype "bidirectional"))
      (node (ref "U$2") (pin "Y6") (pinfunction "X6_Y6") (pintype "bidirectional"))
    )
    (net (code "241") (name "/VREF") (class "Default")
      (node (ref "J1") (pin "H1") (pinfunction "H1_H1") (pintype "bidirectional"))
    )
    (net (code "242") (name "GND") (class "Default")
      (node (ref "C1") (pin "2") (pinfunction "-_2") (pintype "bidirectional"))
      (node (ref "C2") (pin "2") (pinfunction "-_2") (pintype "bidirectional"))
      (node (ref "C3") (pin "2") (pinfunction "-_2") (pintype "bidirectional"))
      (node (ref "CONN1") (pin "2") (pinfunction "2_2") (pintype "passive"))
      (node (ref "CONN1") (pin "3") (pinfunction "2_3") (pintype "passive"))
      (node (ref "CONN1") (pin "4") (pinfunction "2_4") (pintype "passive"))
      (node (ref "CONN1") (pin "5") (pinfunction "2_5") (pintype "passive"))
      (node (ref "CONN2") (pin "2") (pinfunction "2_2") (pintype "passive"))
      (node (ref "CONN2") (pin "3") (pinfunction "2_3") (pintype "passive"))
      (node (ref "CONN2") (pin "4") (pinfunction "2_4") (pintype "passive"))
      (node (ref "CONN2") (pin "5") (pinfunction "2_5") (pintype "passive"))
      (node (ref "CONN3") (pin "2") (pinfunction "2_2") (pintype "passive"))
      (node (ref "CONN3") (pin "3") (pinfunction "2_3") (pintype "passive"))
      (node (ref "CONN3") (pin "4") (pinfunction "2_4") (pintype "passive"))
      (node (ref "CONN3") (pin "5") (pinfunction "2_5") (pintype "passive"))
      (node (ref "CONN4") (pin "2") (pinfunction "2_2") (pintype "passive"))
      (node (ref "CONN4") (pin "3") (pinfunction "2_3") (pintype "passive"))
      (node (ref "CONN4") (pin "4") (pinfunction "2_4") (pintype "passive"))
      (node (ref "CONN4") (pin "5") (pinfunction "2_5") (pintype "passive"))
      (node (ref "C_C1") (pin "2") (pinfunction "2_2") (pintype "passive"))
      (node (ref "C_C2") (pin "2") (pinfunction "2_2") (pintype "passive"))
      (node (ref "C_F") (pin "2") (pinfunction "2_2") (pintype "passive"))
      (node (ref "C_F1") (pin "2") (pinfunction "2_2") (pintype "passive"))
      (node (ref "C_IN") (pin "2") (pinfunction "2_2") (pintype "bidirectional"))
      (node (ref "C_IN1") (pin "2") (pinfunction "2_2") (pintype "bidirectional"))
      (node (ref "C_OUT") (pin "2") (pinfunction "2_2") (pintype "bidirectional"))
      (node (ref "C_OUT1") (pin "2") (pinfunction "2_2") (pintype "bidirectional"))
      (node (ref "C_SS") (pin "2") (pinfunction "2_2") (pintype "passive"))
      (node (ref "C_SS1") (pin "2") (pinfunction "2_2") (pintype "passive"))
      (node (ref "C_VCC") (pin "2") (pinfunction "2_2") (pintype "passive"))
      (node (ref "C_VCC1") (pin "2") (pinfunction "2_2") (pintype "passive"))
      (node (ref "IC1") (pin "3") (pinfunction "GND_3") (pintype "power_in"))
      (node (ref "IC2") (pin "3") (pinfunction "GND_3") (pintype "power_in"))
      (node (ref "IC3") (pin "3") (pinfunction "GND_3") (pintype "power_in"))
      (node (ref "J1") (pin "A1") (pinfunction "A1_A1") (pintype "bidirectional"))
      (node (ref "J1") (pin "A12") (pinfunction "A12_A12") (pintype "bidirectional"))
      (node (ref "J1") (pin "A13") (pinfunction "A13_A13") (pintype "bidirectional"))
      (node (ref "J1") (pin "A16") (pinfunction "A16_A16") (pintype "bidirectional"))
      (node (ref "J1") (pin "A17") (pinfunction "A17_A17") (pintype "bidirectional"))
      (node (ref "J1") (pin "A20") (pinfunction "A20_A20") (pintype "bidirectional"))
      (node (ref "J1") (pin "A21") (pinfunction "A21_A21") (pintype "bidirectional"))
      (node (ref "J1") (pin "A24") (pinfunction "A24_A24") (pintype "bidirectional"))
      (node (ref "J1") (pin "A25") (pinfunction "A25_A25") (pintype "bidirectional"))
      (node (ref "J1") (pin "A28") (pinfunction "A28_A28") (pintype "bidirectional"))
      (node (ref "J1") (pin "A29") (pinfunction "A29_A29") (pintype "bidirectional"))
      (node (ref "J1") (pin "A32") (pinfunction "A32_A32") (pintype "bidirectional"))
      (node (ref "J1") (pin "A33") (pinfunction "A33_A33") (pintype "bidirectional"))
      (node (ref "J1") (pin "A36") (pinfunction "A36_A36") (pintype "bidirectional"))
      (node (ref "J1") (pin "A37") (pinfunction "A37_A37") (pintype "bidirectional"))
      (node (ref "J1") (pin "A4") (pinfunction "A4_A4") (pintype "bidirectional"))
      (node (ref "J1") (pin "A40") (pinfunction "A40_A40") (pintype "bidirectional"))
      (node (ref "J1") (pin "A5") (pinfunction "A5_A5") (pintype "bidirectional"))
      (node (ref "J1") (pin "A8") (pinfunction "A8_A8") (pintype "bidirectional"))
      (node (ref "J1") (pin "A9") (pinfunction "A9_A9") (pintype "bidirectional"))
      (node (ref "J1") (pin "B10") (pinfunction "B10_B10") (pintype "bidirectional"))
      (node (ref "J1") (pin "B11") (pinfunction "B11_B11") (pintype "bidirectional"))
      (node (ref "J1") (pin "B14") (pinfunction "B14_B14") (pintype "bidirectional"))
      (node (ref "J1") (pin "B15") (pinfunction "B15_B15") (pintype "bidirectional"))
      (node (ref "J1") (pin "B18") (pinfunction "B18_B18") (pintype "bidirectional"))
      (node (ref "J1") (pin "B19") (pinfunction "B19_B19") (pintype "bidirectional"))
      (node (ref "J1") (pin "B2") (pinfunction "B2_B2") (pintype "bidirectional"))
      (node (ref "J1") (pin "B22") (pinfunction "B22_B22") (pintype "bidirectional"))
      (node (ref "J1") (pin "B23") (pinfunction "B23_B23") (pintype "bidirectional"))
      (node (ref "J1") (pin "B26") (pinfunction "B26_B26") (pintype "bidirectional"))
      (node (ref "J1") (pin "B27") (pinfunction "B27_B27") (pintype "bidirectional"))
      (node (ref "J1") (pin "B3") (pinfunction "B3_B3") (pintype "bidirectional"))
      (node (ref "J1") (pin "B30") (pinfunction "B30_B30") (pintype "bidirectional"))
      (node (ref "J1") (pin "B31") (pinfunction "B31_B31") (pintype "bidirectional"))
      (node (ref "J1") (pin "B34") (pinfunction "B34_B34") (pintype "bidirectional"))
      (node (ref "J1") (pin "B35") (pinfunction "B35_B35") (pintype "bidirectional"))
      (node (ref "J1") (pin "B38") (pinfunction "B38_B38") (pintype "bidirectional"))
      (node (ref "J1") (pin "B39") (pinfunction "B39_B39") (pintype "bidirectional"))
      (node (ref "J1") (pin "B6") (pinfunction "B6_B6") (pintype "bidirectional"))
      (node (ref "J1") (pin "B7") (pinfunction "B7_B7") (pintype "bidirectional"))
      (node (ref "J1") (pin "C1") (pinfunction "C1_C1") (pintype "bidirectional"))
      (node (ref "J1") (pin "C12") (pinfunction "C12_C12") (pintype "bidirectional"))
      (node (ref "J1") (pin "C13") (pinfunction "C13_C13") (pintype "bidirectional"))
      (node (ref "J1") (pin "C16") (pinfunction "C16_C16") (pintype "bidirectional"))
      (node (ref "J1") (pin "C17") (pinfunction "C17_C17") (pintype "bidirectional"))
      (node (ref "J1") (pin "C20") (pinfunction "C20_C20") (pintype "bidirectional"))
      (node (ref "J1") (pin "C21") (pinfunction "C21_C21") (pintype "bidirectional"))
      (node (ref "J1") (pin "C24") (pinfunction "C24_C24") (pintype "bidirectional"))
      (node (ref "J1") (pin "C25") (pinfunction "C25_C25") (pintype "bidirectional"))
      (node (ref "J1") (pin "C28") (pinfunction "C28_C28") (pintype "bidirectional"))
      (node (ref "J1") (pin "C29") (pinfunction "C29_C29") (pintype "bidirectional"))
      (node (ref "J1") (pin "C32") (pinfunction "C32_C32") (pintype "bidirectional"))
      (node (ref "J1") (pin "C33") (pinfunction "C33_C33") (pintype "bidirectional"))
      (node (ref "J1") (pin "C34") (pinfunction "C34_C34") (pintype "bidirectional"))
      (node (ref "J1") (pin "C36") (pinfunction "C36_C36") (pintype "bidirectional"))
      (node (ref "J1") (pin "C38") (pinfunction "C38_C38") (pintype "bidirectional"))
      (node (ref "J1") (pin "C4") (pinfunction "C4_C4") (pintype "bidirectional"))
      (node (ref "J1") (pin "C40") (pinfunction "C40_C40") (pintype "bidirectional"))
      (node (ref "J1") (pin "C5") (pinfunction "C5_C5") (pintype "bidirectional"))
      (node (ref "J1") (pin "C8") (pinfunction "C8_C8") (pintype "bidirectional"))
      (node (ref "J1") (pin "C9") (pinfunction "C9_C9") (pintype "bidirectional"))
      (node (ref "J1") (pin "D10") (pinfunction "D10_D10") (pintype "bidirectional"))
      (node (ref "J1") (pin "D13") (pinfunction "D13_D13") (pintype "bidirectional"))
      (node (ref "J1") (pin "D16") (pinfunction "D16_D16") (pintype "bidirectional"))
      (node (ref "J1") (pin "D19") (pinfunction "D19_D19") (pintype "bidirectional"))
      (node (ref "J1") (pin "D2") (pinfunction "D2_D2") (pintype "bidirectional"))
      (node (ref "J1") (pin "D22") (pinfunction "D22_D22") (pintype "bidirectional"))
      (node (ref "J1") (pin "D25") (pinfunction "D25_D25") (pintype "bidirectional"))
      (node (ref "J1") (pin "D28") (pinfunction "D28_D28") (pintype "bidirectional"))
      (node (ref "J1") (pin "D3") (pinfunction "D3_D3") (pintype "bidirectional"))
      (node (ref "J1") (pin "D35") (pinfunction "D35_D35") (pintype "bidirectional"))
      (node (ref "J1") (pin "D37") (pinfunction "D37_D37") (pintype "bidirectional"))
      (node (ref "J1") (pin "D39") (pinfunction "D39_D39") (pintype "bidirectional"))
      (node (ref "J1") (pin "D6") (pinfunction "D6_D6") (pintype "bidirectional"))
      (node (ref "J1") (pin "D7") (pinfunction "D7_D7") (pintype "bidirectional"))
      (node (ref "J1") (pin "E1") (pinfunction "E1_E1") (pintype "bidirectional"))
      (node (ref "J1") (pin "E11") (pinfunction "E11_E11") (pintype "bidirectional"))
      (node (ref "J1") (pin "E14") (pinfunction "E14_E14") (pintype "bidirectional"))
      (node (ref "J1") (pin "E17") (pinfunction "E17_E17") (pintype "bidirectional"))
      (node (ref "J1") (pin "E20") (pinfunction "E20_E20") (pintype "bidirectional"))
      (node (ref "J1") (pin "E23") (pinfunction "E23_E23") (pintype "bidirectional"))
      (node (ref "J1") (pin "E26") (pinfunction "E26_E26") (pintype "bidirectional"))
      (node (ref "J1") (pin "E29") (pinfunction "E29_E29") (pintype "bidirectional"))
      (node (ref "J1") (pin "E32") (pinfunction "E32_E32") (pintype "bidirectional"))
      (node (ref "J1") (pin "E35") (pinfunction "E35_E35") (pintype "bidirectional"))
      (node (ref "J1") (pin "E38") (pinfunction "E38_E38") (pintype "bidirectional"))
      (node (ref "J1") (pin "E4") (pinfunction "E4_E4") (pintype "bidirectional"))
      (node (ref "J1") (pin "E40") (pinfunction "E40_E40") (pintype "bidirectional"))
      (node (ref "J1") (pin "E5") (pinfunction "E5_E5") (pintype "bidirectional"))
      (node (ref "J1") (pin "E8") (pinfunction "E8_E8") (pintype "bidirectional"))
      (node (ref "J1") (pin "F12") (pinfunction "F12_F12") (pintype "bidirectional"))
      (node (ref "J1") (pin "F15") (pinfunction "F15_F15") (pintype "bidirectional"))
      (node (ref "J1") (pin "F18") (pinfunction "F18_F18") (pintype "bidirectional"))
      (node (ref "J1") (pin "F2") (pinfunction "F2_F2") (pintype "bidirectional"))
      (node (ref "J1") (pin "F21") (pinfunction "F21_F21") (pintype "bidirectional"))
      (node (ref "J1") (pin "F24") (pinfunction "F24_F24") (pintype "bidirectional"))
      (node (ref "J1") (pin "F27") (pinfunction "F27_F27") (pintype "bidirectional"))
      (node (ref "J1") (pin "F3") (pinfunction "F3_F3") (pintype "bidirectional"))
      (node (ref "J1") (pin "F30") (pinfunction "F30_F30") (pintype "bidirectional"))
      (node (ref "J1") (pin "F33") (pinfunction "F33_F33") (pintype "bidirectional"))
      (node (ref "J1") (pin "F36") (pinfunction "F36_F36") (pintype "bidirectional"))
      (node (ref "J1") (pin "F39") (pinfunction "F39_F39") (pintype "bidirectional"))
      (node (ref "J1") (pin "F6") (pinfunction "F6_F6") (pintype "bidirectional"))
      (node (ref "J1") (pin "F9") (pinfunction "F9_F9") (pintype "bidirectional"))
      (node (ref "J1") (pin "G1") (pinfunction "G1_G1") (pintype "bidirectional"))
      (node (ref "J1") (pin "G11") (pinfunction "G11_G11") (pintype "bidirectional"))
      (node (ref "J1") (pin "G14") (pinfunction "G14_G14") (pintype "bidirectional"))
      (node (ref "J1") (pin "G17") (pinfunction "G17_G17") (pintype "bidirectional"))
      (node (ref "J1") (pin "G20") (pinfunction "G20_G20") (pintype "bidirectional"))
      (node (ref "J1") (pin "G23") (pinfunction "G23_G23") (pintype "bidirectional"))
      (node (ref "J1") (pin "G26") (pinfunction "G26_G26") (pintype "bidirectional"))
      (node (ref "J1") (pin "G29") (pinfunction "G29_G29") (pintype "bidirectional"))
      (node (ref "J1") (pin "G32") (pinfunction "G32_G32") (pintype "bidirectional"))
      (node (ref "J1") (pin "G35") (pinfunction "G35_G35") (pintype "bidirectional"))
      (node (ref "J1") (pin "G38") (pinfunction "G38_G38") (pintype "bidirectional"))
      (node (ref "J1") (pin "G4") (pinfunction "G4_G4") (pintype "bidirectional"))
      (node (ref "J1") (pin "G40") (pinfunction "G40_G40") (pintype "bidirectional"))
      (node (ref "J1") (pin "G5") (pinfunction "G5_G5") (pintype "bidirectional"))
      (node (ref "J1") (pin "G8") (pinfunction "G8_G8") (pintype "bidirectional"))
      (node (ref "J1") (pin "H12") (pinfunction "H12_H12") (pintype "bidirectional"))
      (node (ref "J1") (pin "H15") (pinfunction "H15_H15") (pintype "bidirectional"))
      (node (ref "J1") (pin "H18") (pinfunction "H18_H18") (pintype "bidirectional"))
      (node (ref "J1") (pin "H21") (pinfunction "H21_H21") (pintype "bidirectional"))
      (node (ref "J1") (pin "H24") (pinfunction "H24_H24") (pintype "bidirectional"))
      (node (ref "J1") (pin "H27") (pinfunction "H27_H27") (pintype "bidirectional"))
      (node (ref "J1") (pin "H3") (pinfunction "H3_H3") (pintype "bidirectional"))
      (node (ref "J1") (pin "H30") (pinfunction "H30_H30") (pintype "bidirectional"))
      (node (ref "J1") (pin "H33") (pinfunction "H33_H33") (pintype "bidirectional"))
      (node (ref "J1") (pin "H36") (pinfunction "H36_H36") (pintype "bidirectional"))
      (node (ref "J1") (pin "H39") (pinfunction "H39_H39") (pintype "bidirectional"))
      (node (ref "J1") (pin "H6") (pinfunction "H6_H6") (pintype "bidirectional"))
      (node (ref "J1") (pin "H9") (pinfunction "H9_H9") (pintype "bidirectional"))
      (node (ref "J1") (pin "J1") (pinfunction "J1_J1") (pintype "bidirectional"))
      (node (ref "J1") (pin "J11") (pinfunction "J11_J11") (pintype "bidirectional"))
      (node (ref "J1") (pin "J14") (pinfunction "J14_J14") (pintype "bidirectional"))
      (node (ref "J1") (pin "J17") (pinfunction "J17_J17") (pintype "bidirectional"))
      (node (ref "J1") (pin "J20") (pinfunction "J20_J20") (pintype "bidirectional"))
      (node (ref "J1") (pin "J23") (pinfunction "J23_J23") (pintype "bidirectional"))
      (node (ref "J1") (pin "J26") (pinfunction "J26_J26") (pintype "bidirectional"))
      (node (ref "J1") (pin "J29") (pinfunction "J29_J29") (pintype "bidirectional"))
      (node (ref "J1") (pin "J32") (pinfunction "J32_J32") (pintype "bidirectional"))
      (node (ref "J1") (pin "J35") (pinfunction "J35_J35") (pintype "bidirectional"))
      (node (ref "J1") (pin "J38") (pinfunction "J38_J38") (pintype "bidirectional"))
      (node (ref "J1") (pin "J4") (pinfunction "J4_J4") (pintype "bidirectional"))
      (node (ref "J1") (pin "J40") (pinfunction "J40_J40") (pintype "bidirectional"))
      (node (ref "J1") (pin "J5") (pinfunction "J5_J5") (pintype "bidirectional"))
      (node (ref "J1") (pin "J8") (pinfunction "J8_J8") (pintype "bidirectional"))
      (node (ref "J1") (pin "K12") (pinfunction "K12_K12") (pintype "bidirectional"))
      (node (ref "J1") (pin "K15") (pinfunction "K15_K15") (pintype "bidirectional"))
      (node (ref "J1") (pin "K18") (pinfunction "K18_K18") (pintype "bidirectional"))
      (node (ref "J1") (pin "K2") (pinfunction "K2_K2") (pintype "bidirectional"))
      (node (ref "J1") (pin "K21") (pinfunction "K21_K21") (pintype "bidirectional"))
      (node (ref "J1") (pin "K24") (pinfunction "K24_K24") (pintype "bidirectional"))
      (node (ref "J1") (pin "K27") (pinfunction "K27_K27") (pintype "bidirectional"))
      (node (ref "J1") (pin "K3") (pinfunction "K3_K3") (pintype "bidirectional"))
      (node (ref "J1") (pin "K30") (pinfunction "K30_K30") (pintype "bidirectional"))
      (node (ref "J1") (pin "K33") (pinfunction "K33_K33") (pintype "bidirectional"))
      (node (ref "J1") (pin "K36") (pinfunction "K36_K36") (pintype "bidirectional"))
      (node (ref "J1") (pin "K39") (pinfunction "K39_K39") (pintype "bidirectional"))
      (node (ref "J1") (pin "K6") (pinfunction "K6_K6") (pintype "bidirectional"))
      (node (ref "J1") (pin "K9") (pinfunction "K9_K9") (pintype "bidirectional"))
      (node (ref "J2") (pin "2") (pinfunction "2_2") (pintype "passive"))
      (node (ref "J2") (pin "3") (pinfunction "3_3") (pintype "passive"))
      (node (ref "J2") (pin "4") (pinfunction "SHIELD_4") (pintype "passive"))
      (node (ref "J2") (pin "5") (pinfunction "SHIELD_5") (pintype "passive"))
      (node (ref "R_FB2") (pin "2") (pinfunction "2_2") (pintype "passive"))
      (node (ref "SV1") (pin "1") (pinfunction "1_1") (pintype "passive"))
      (node (ref "U$1") (pin "10") (pinfunction "PGND_10") (pintype "bidirectional"))
      (node (ref "U$1") (pin "11") (pinfunction "PGND_11") (pintype "bidirectional"))
      (node (ref "U$1") (pin "15") (pinfunction "AGND_15") (pintype "bidirectional"))
      (node (ref "U$1") (pin "16") (pinfunction "NC_16") (pintype "bidirectional"))
      (node (ref "U$1") (pin "17") (pinfunction "EP_17") (pintype "bidirectional"))
      (node (ref "U$1") (pin "5") (pinfunction "NC_5") (pintype "bidirectional"))
      (node (ref "U$2") (pin "A1") (pinfunction "A1_A1") (pintype "bidirectional"))
      (node (ref "U$2") (pin "A12") (pinfunction "A12_A12") (pintype "bidirectional"))
      (node (ref "U$2") (pin "A15") (pinfunction "A15_A15") (pintype "bidirectional"))
      (node (ref "U$2") (pin "A19") (pinfunction "A19_A19") (pintype "bidirectional"))
      (node (ref "U$2") (pin "A22") (pinfunction "A22_A22") (pintype "bidirectional"))
      (node (ref "U$2") (pin "A4") (pinfunction "A4_A4") (pintype "bidirectional"))
      (node (ref "U$2") (pin "A9") (pinfunction "A9_A9") (pintype "bidirectional"))
      (node (ref "U$2") (pin "AA10") (pinfunction "Y10_AA10") (pintype "bidirectional"))
      (node (ref "U$2") (pin "AA13") (pinfunction "Y13_AA13") (pintype "bidirectional"))
      (node (ref "U$2") (pin "AA20") (pinfunction "Y20_AA20") (pintype "bidirectional"))
      (node (ref "U$2") (pin "AA3") (pinfunction "Y3_AA3") (pintype "bidirectional"))
      (node (ref "U$2") (pin "AB1") (pinfunction "Z1_AB1") (pintype "bidirectional"))
      (node (ref "U$2") (pin "AB10") (pinfunction "Z10_AB10") (pintype "bidirectional"))
      (node (ref "U$2") (pin "AB13") (pinfunction "Z13_AB13") (pintype "bidirectional"))
      (node (ref "U$2") (pin "AB16") (pinfunction "Z16_AB16") (pintype "bidirectional"))
      (node (ref "U$2") (pin "AB19") (pinfunction "Z19_AB19") (pintype "bidirectional"))
      (node (ref "U$2") (pin "AB22") (pinfunction "Z22_AB22") (pintype "bidirectional"))
      (node (ref "U$2") (pin "AB4") (pinfunction "Z4_AB4") (pintype "bidirectional"))
      (node (ref "U$2") (pin "AB7") (pinfunction "Z7_AB7") (pintype "bidirectional"))
      (node (ref "U$2") (pin "B10") (pinfunction "B10_B10") (pintype "bidirectional"))
      (node (ref "U$2") (pin "B11") (pinfunction "B11_B11") (pintype "bidirectional"))
      (node (ref "U$2") (pin "B13") (pinfunction "B13_B13") (pintype "bidirectional"))
      (node (ref "U$2") (pin "B14") (pinfunction "B14_B14") (pintype "bidirectional"))
      (node (ref "U$2") (pin "B3") (pinfunction "B3_B3") (pintype "bidirectional"))
      (node (ref "U$2") (pin "C13") (pinfunction "C13_C13") (pintype "bidirectional"))
      (node (ref "U$2") (pin "C14") (pinfunction "C14_C14") (pintype "bidirectional"))
      (node (ref "U$2") (pin "C2") (pinfunction "C2_C2") (pintype "bidirectional"))
      (node (ref "U$2") (pin "C20") (pinfunction "C20_C20") (pintype "bidirectional"))
      (node (ref "U$2") (pin "C21") (pinfunction "C21_C21") (pintype "bidirectional"))
      (node (ref "U$2") (pin "C3") (pinfunction "C3_C3") (pintype "bidirectional"))
      (node (ref "U$2") (pin "D1") (pinfunction "D1_D1") (pintype "bidirectional"))
      (node (ref "U$2") (pin "D10") (pinfunction "D10_D10") (pintype "bidirectional"))
      (node (ref "U$2") (pin "D14") (pinfunction "D14_D14") (pintype "bidirectional"))
      (node (ref "U$2") (pin "D17") (pinfunction "D17_D17") (pintype "bidirectional"))
      (node (ref "U$2") (pin "D18") (pinfunction "D18_D18") (pintype "bidirectional"))
      (node (ref "U$2") (pin "D21") (pinfunction "D21_D21") (pintype "bidirectional"))
      (node (ref "U$2") (pin "D22") (pinfunction "D22_D22") (pintype "bidirectional"))
      (node (ref "U$2") (pin "D3") (pinfunction "D3_D3") (pintype "bidirectional"))
      (node (ref "U$2") (pin "D6") (pinfunction "D6_D6") (pintype "bidirectional"))
      (node (ref "U$2") (pin "D9") (pinfunction "D9_D9") (pintype "bidirectional"))
      (node (ref "U$2") (pin "E4") (pinfunction "E4_E4") (pintype "bidirectional"))
      (node (ref "U$2") (pin "F19") (pinfunction "F19_F19") (pintype "bidirectional"))
      (node (ref "U$2") (pin "F4") (pinfunction "F4_F4") (pintype "bidirectional"))
      (node (ref "U$2") (pin "G1") (pinfunction "G1_G1") (pintype "bidirectional"))
      (node (ref "U$2") (pin "G19") (pinfunction "G19_G19") (pintype "bidirectional"))
      (node (ref "U$2") (pin "G22") (pinfunction "G22_G22") (pintype "bidirectional"))
      (node (ref "U$2") (pin "G4") (pinfunction "G4_G4") (pintype "bidirectional"))
      (node (ref "U$2") (pin "H15") (pinfunction "H15_H15") (pintype "bidirectional"))
      (node (ref "U$2") (pin "H8") (pinfunction "H8_H8") (pintype "bidirectional"))
      (node (ref "U$2") (pin "J10") (pinfunction "J10_J10") (pintype "bidirectional"))
      (node (ref "U$2") (pin "J11") (pinfunction "J11_J11") (pintype "bidirectional"))
      (node (ref "U$2") (pin "J12") (pinfunction "J12_J12") (pintype "bidirectional"))
      (node (ref "U$2") (pin "J13") (pinfunction "J13_J13") (pintype "bidirectional"))
      (node (ref "U$2") (pin "J14") (pinfunction "J14_J14") (pintype "bidirectional"))
      (node (ref "U$2") (pin "J4") (pinfunction "J4_J4") (pintype "bidirectional"))
      (node (ref "U$2") (pin "J9") (pinfunction "J9_J9") (pintype "bidirectional"))
      (node (ref "U$2") (pin "K1") (pinfunction "K1_K1") (pintype "bidirectional"))
      (node (ref "U$2") (pin "K10") (pinfunction "K10_K10") (pintype "bidirectional"))
      (node (ref "U$2") (pin "K11") (pinfunction "K11_K11") (pintype "bidirectional"))
      (node (ref "U$2") (pin "K12") (pinfunction "K12_K12") (pintype "bidirectional"))
      (node (ref "U$2") (pin "K13") (pinfunction "K13_K13") (pintype "bidirectional"))
      (node (ref "U$2") (pin "K14") (pinfunction "K14_K14") (pintype "bidirectional"))
      (node (ref "U$2") (pin "K19") (pinfunction "K19_K19") (pintype "bidirectional"))
      (node (ref "U$2") (pin "K22") (pinfunction "K22_K22") (pintype "bidirectional"))
      (node (ref "U$2") (pin "K4") (pinfunction "K4_K4") (pintype "bidirectional"))
      (node (ref "U$2") (pin "K9") (pinfunction "K9_K9") (pintype "bidirectional"))
      (node (ref "U$2") (pin "L10") (pinfunction "L10_L10") (pintype "bidirectional"))
      (node (ref "U$2") (pin "L11") (pinfunction "L11_L11") (pintype "bidirectional"))
      (node (ref "U$2") (pin "L12") (pinfunction "L12_L12") (pintype "bidirectional"))
      (node (ref "U$2") (pin "L13") (pinfunction "L13_L13") (pintype "bidirectional"))
      (node (ref "U$2") (pin "L14") (pinfunction "L14_L14") (pintype "bidirectional"))
      (node (ref "U$2") (pin "L2") (pinfunction "L2_L2") (pintype "bidirectional"))
      (node (ref "U$2") (pin "L21") (pinfunction "L21_L21") (pintype "bidirectional"))
      (node (ref "U$2") (pin "L4") (pinfunction "L4_L4") (pintype "bidirectional"))
      (node (ref "U$2") (pin "L9") (pinfunction "L9_L9") (pintype "bidirectional"))
      (node (ref "U$2") (pin "M10") (pinfunction "M10_M10") (pintype "bidirectional"))
      (node (ref "U$2") (pin "M11") (pinfunction "M11_M11") (pintype "bidirectional"))
      (node (ref "U$2") (pin "M12") (pinfunction "M12_M12") (pintype "bidirectional"))
      (node (ref "U$2") (pin "M13") (pinfunction "M13_M13") (pintype "bidirectional"))
      (node (ref "U$2") (pin "M14") (pinfunction "M14_M14") (pintype "bidirectional"))
      (node (ref "U$2") (pin "M2") (pinfunction "M2_M2") (pintype "bidirectional"))
      (node (ref "U$2") (pin "M20") (pinfunction "M20_M20") (pintype "bidirectional"))
      (node (ref "U$2") (pin "M21") (pinfunction "M21_M21") (pintype "bidirectional"))
      (node (ref "U$2") (pin "M9") (pinfunction "M9_M9") (pintype "bidirectional"))
      (node (ref "U$2") (pin "N1") (pinfunction "N1_N1") (pintype "bidirectional"))
      (node (ref "U$2") (pin "N10") (pinfunction "N10_N10") (pintype "bidirectional"))
      (node (ref "U$2") (pin "N11") (pinfunction "N11_N11") (pintype "bidirectional"))
      (node (ref "U$2") (pin "N12") (pinfunction "N12_N12") (pintype "bidirectional"))
      (node (ref "U$2") (pin "N13") (pinfunction "N13_N13") (pintype "bidirectional"))
      (node (ref "U$2") (pin "N14") (pinfunction "N14_N14") (pintype "bidirectional"))
      (node (ref "U$2") (pin "N19") (pinfunction "N19_N19") (pintype "bidirectional"))
      (node (ref "U$2") (pin "N22") (pinfunction "N22_N22") (pintype "bidirectional"))
      (node (ref "U$2") (pin "N4") (pinfunction "N4_N4") (pintype "bidirectional"))
      (node (ref "U$2") (pin "N9") (pinfunction "N9_N9") (pintype "bidirectional"))
      (node (ref "U$2") (pin "P10") (pinfunction "P10_P10") (pintype "bidirectional"))
      (node (ref "U$2") (pin "P11") (pinfunction "P11_P11") (pintype "bidirectional"))
      (node (ref "U$2") (pin "P12") (pinfunction "P12_P12") (pintype "bidirectional"))
      (node (ref "U$2") (pin "P13") (pinfunction "P13_P13") (pintype "bidirectional"))
      (node (ref "U$2") (pin "P14") (pinfunction "P14_P14") (pintype "bidirectional"))
      (node (ref "U$2") (pin "P9") (pinfunction "P9_P9") (pintype "bidirectional"))
      (node (ref "U$2") (pin "R15") (pinfunction "R15_R15") (pintype "bidirectional"))
      (node (ref "U$2") (pin "R2") (pinfunction "R2_R2") (pintype "bidirectional"))
      (node (ref "U$2") (pin "R8") (pinfunction "R8_R8") (pintype "bidirectional"))
      (node (ref "U$2") (pin "T1") (pinfunction "T1_T1") (pintype "bidirectional"))
      (node (ref "U$2") (pin "T19") (pinfunction "T19_T19") (pintype "bidirectional"))
      (node (ref "U$2") (pin "T2") (pinfunction "T2_T2") (pintype "bidirectional"))
      (node (ref "U$2") (pin "T22") (pinfunction "T22_T22") (pintype "bidirectional"))
      (node (ref "U$2") (pin "U19") (pinfunction "U19_U19") (pintype "bidirectional"))
      (node (ref "U$2") (pin "U4") (pinfunction "U4_U4") (pintype "bidirectional"))
      (node (ref "U$2") (pin "V19") (pinfunction "V19_V19") (pintype "bidirectional"))
      (node (ref "U$2") (pin "V4") (pinfunction "V4_V4") (pintype "bidirectional"))
      (node (ref "U$2") (pin "W1") (pinfunction "W1_W1") (pintype "bidirectional"))
      (node (ref "U$2") (pin "W10") (pinfunction "W10_W10") (pintype "bidirectional"))
      (node (ref "U$2") (pin "W13") (pinfunction "W13_W13") (pintype "bidirectional"))
      (node (ref "U$2") (pin "W16") (pinfunction "W16_W16") (pintype "bidirectional"))
      (node (ref "U$2") (pin "W17") (pinfunction "W17_W17") (pintype "bidirectional"))
      (node (ref "U$2") (pin "W2") (pinfunction "W2_W2") (pintype "bidirectional"))
      (node (ref "U$2") (pin "W22") (pinfunction "W22_W22") (pintype "bidirectional"))
      (node (ref "U$2") (pin "W6") (pinfunction "W6_W6") (pintype "bidirectional"))
      (node (ref "U$2") (pin "W7") (pinfunction "W7_W7") (pintype "bidirectional"))
      (node (ref "U$2") (pin "Y10") (pinfunction "X10_Y10") (pintype "bidirectional"))
      (node (ref "U$2") (pin "Y13") (pinfunction "X13_Y13") (pintype "bidirectional"))
      (node (ref "U$2") (pin "Y2") (pinfunction "X2_Y2") (pintype "bidirectional"))
      (node (ref "U$2") (pin "Y20") (pinfunction "X20_Y20") (pintype "bidirectional"))
      (node (ref "U$2") (pin "Y3") (pinfunction "X3_Y3") (pintype "bidirectional"))
      (node (ref "U$3") (pin "10") (pinfunction "PGND_10") (pintype "bidirectional"))
      (node (ref "U$3") (pin "11") (pinfunction "PGND_11") (pintype "bidirectional"))
      (node (ref "U$3") (pin "15") (pinfunction "AGND_15") (pintype "bidirectional"))
      (node (ref "U$3") (pin "16") (pinfunction "NC_16") (pintype "bidirectional"))
      (node (ref "U$3") (pin "17") (pinfunction "EP_17") (pintype "bidirectional"))
      (node (ref "U$3") (pin "5") (pinfunction "NC_5") (pintype "bidirectional"))
    )
    (net (code "243") (name "Net-(C_C1-Pad1)") (class "Default")
      (node (ref "C_C1") (pin "1") (pinfunction "1_1") (pintype "passive"))
      (node (ref "R_C1") (pin "1") (pinfunction "1_1") (pintype "passive"))
    )
    (net (code "244") (name "Net-(C_C2-Pad1)") (class "Default")
      (node (ref "C_C2") (pin "1") (pinfunction "1_1") (pintype "passive"))
      (node (ref "R_C2") (pin "1") (pinfunction "1_1") (pintype "passive"))
    )
    (net (code "245") (name "Net-(IC1A-O)") (class "Default")
      (node (ref "IC1") (pin "4") (pinfunction "O_4") (pintype "output"))
      (node (ref "IC3") (pin "1") (pinfunction "I0_1") (pintype "input"))
    )
    (net (code "246") (name "Net-(IC2A-O)") (class "Default")
      (node (ref "IC2") (pin "4") (pinfunction "O_4") (pintype "output"))
      (node (ref "IC3") (pin "2") (pinfunction "I1_2") (pintype "input"))
    )
    (net (code "247") (name "Net-(L-Pad1)") (class "Default")
      (node (ref "L") (pin "1") (pinfunction "1_1") (pintype "passive"))
      (node (ref "U$1") (pin "8") (pinfunction "SW_8") (pintype "bidirectional"))
      (node (ref "U$1") (pin "9") (pinfunction "SW_9") (pintype "bidirectional"))
    )
    (net (code "248") (name "Net-(L_1-Pad1)") (class "Default")
      (node (ref "L_1") (pin "1") (pinfunction "1_1") (pintype "passive"))
      (node (ref "U$3") (pin "8") (pinfunction "SW_8") (pintype "bidirectional"))
      (node (ref "U$3") (pin "9") (pinfunction "SW_9") (pintype "bidirectional"))
    )
    (net (code "249") (name "Net-(U$1-AVIN)") (class "Default")
      (node (ref "C_F") (pin "1") (pinfunction "1_1") (pintype "passive"))
      (node (ref "R_F") (pin "1") (pinfunction "1_1") (pintype "bidirectional"))
      (node (ref "U$1") (pin "14") (pinfunction "AVIN_14") (pintype "bidirectional"))
    )
    (net (code "250") (name "Net-(U$1-COMP)") (class "Default")
      (node (ref "R_C1") (pin "2") (pinfunction "2_2") (pintype "passive"))
      (node (ref "U$1") (pin "4") (pinfunction "COMP_4") (pintype "bidirectional"))
    )
    (net (code "251") (name "Net-(U$1-SS{slash}TRK)") (class "Default")
      (node (ref "C_SS") (pin "1") (pinfunction "1_1") (pintype "passive"))
      (node (ref "U$1") (pin "1") (pinfunction "SS/TRK_1") (pintype "bidirectional"))
    )
    (net (code "252") (name "Net-(U$1-VCC)") (class "Default")
      (node (ref "C_VCC") (pin "1") (pinfunction "1_1") (pintype "passive"))
      (node (ref "U$1") (pin "13") (pinfunction "VCC_13") (pintype "bidirectional"))
    )
    (net (code "253") (name "Net-(U$3-AVIN)") (class "Default")
      (node (ref "C_F1") (pin "1") (pinfunction "1_1") (pintype "passive"))
      (node (ref "R_F1") (pin "1") (pinfunction "1_1") (pintype "bidirectional"))
      (node (ref "U$3") (pin "14") (pinfunction "AVIN_14") (pintype "bidirectional"))
    )
    (net (code "254") (name "Net-(U$3-COMP)") (class "Default")
      (node (ref "R_C2") (pin "2") (pinfunction "2_2") (pintype "passive"))
      (node (ref "U$3") (pin "4") (pinfunction "COMP_4") (pintype "bidirectional"))
    )
    (net (code "255") (name "Net-(U$3-FB)") (class "Default")
      (node (ref "R_FB1") (pin "2") (pinfunction "2_2") (pintype "passive"))
      (node (ref "R_FB2") (pin "1") (pinfunction "1_1") (pintype "passive"))
      (node (ref "U$3") (pin "2") (pinfunction "FB_2") (pintype "bidirectional"))
    )
    (net (code "256") (name "Net-(U$3-SS{slash}TRK)") (class "Default")
      (node (ref "C_SS1") (pin "1") (pinfunction "1_1") (pintype "passive"))
      (node (ref "U$3") (pin "1") (pinfunction "SS/TRK_1") (pintype "bidirectional"))
    )
    (net (code "257") (name "Net-(U$3-VCC)") (class "Default")
      (node (ref "C_VCC1") (pin "1") (pinfunction "1_1") (pintype "passive"))
      (node (ref "U$3") (pin "13") (pinfunction "VCC_13") (pintype "bidirectional"))
    )
    (net (code "258") (name "unconnected-(J1-PadB40)") (class "Default")
      (node (ref "J1") (pin "B40") (pinfunction "B40_B40") (pintype "bidirectional"))
    )
    (net (code "259") (name "unconnected-(J1-PadJ39)") (class "Default")
      (node (ref "J1") (pin "J39") (pinfunction "J39_J39") (pintype "bidirectional"))
    )
    (net (code "260") (name "unconnected-(J1-PadK1)") (class "Default")
      (node (ref "J1") (pin "K1") (pinfunction "K1_K1") (pintype "bidirectional"))
    )
    (net (code "261") (name "unconnected-(J1-PadK40)") (class "Default")
      (node (ref "J1") (pin "K40") (pinfunction "K40_K40") (pintype "bidirectional"))
    )
    (net (code "262") (name "unconnected-(U$2-PadA3)") (class "Default")
      (node (ref "U$2") (pin "A3") (pinfunction "A3_A3") (pintype "bidirectional"))
    )
    (net (code "263") (name "unconnected-(U$2-PadA7)") (class "Default")
      (node (ref "U$2") (pin "A7") (pinfunction "A7_A7") (pintype "bidirectional"))
    )
    (net (code "264") (name "unconnected-(U$2-PadA13)") (class "Default")
      (node (ref "U$2") (pin "A13") (pinfunction "A13_A13") (pintype "bidirectional"))
    )
    (net (code "265") (name "unconnected-(U$2-PadA14)") (class "Default")
      (node (ref "U$2") (pin "A14") (pinfunction "A14_A14") (pintype "bidirectional"))
    )
    (net (code "266") (name "unconnected-(U$2-PadA16)") (class "Default")
      (node (ref "U$2") (pin "A16") (pinfunction "A16_A16") (pintype "bidirectional"))
    )
    (net (code "267") (name "unconnected-(U$2-PadA17)") (class "Default")
      (node (ref "U$2") (pin "A17") (pinfunction "A17_A17") (pintype "bidirectional"))
    )
    (net (code "268") (name "unconnected-(U$2-PadA18)") (class "Default")
      (node (ref "U$2") (pin "A18") (pinfunction "A18_A18") (pintype "bidirectional"))
    )
    (net (code "269") (name "unconnected-(U$2-PadA20)") (class "Default")
      (node (ref "U$2") (pin "A20") (pinfunction "A20_A20") (pintype "bidirectional"))
    )
    (net (code "270") (name "unconnected-(U$2-PadB1)") (class "Default")
      (node (ref "U$2") (pin "B1") (pinfunction "B1_B1") (pintype "bidirectional"))
    )
    (net (code "271") (name "unconnected-(U$2-PadB8)") (class "Default")
      (node (ref "U$2") (pin "B8") (pinfunction "B8_B8") (pintype "bidirectional"))
    )
    (net (code "272") (name "unconnected-(U$2-PadB16)") (class "Default")
      (node (ref "U$2") (pin "B16") (pinfunction "B16_B16") (pintype "bidirectional"))
    )
    (net (code "273") (name "unconnected-(U$2-PadB17)") (class "Default")
      (node (ref "U$2") (pin "B17") (pinfunction "B17_B17") (pintype "bidirectional"))
    )
    (net (code "274") (name "unconnected-(U$2-PadB18)") (class "Default")
      (node (ref "U$2") (pin "B18") (pinfunction "B18_B18") (pintype "bidirectional"))
    )
    (net (code "275") (name "unconnected-(U$2-PadB19)") (class "Default")
      (node (ref "U$2") (pin "B19") (pinfunction "B19_B19") (pintype "bidirectional"))
    )
    (net (code "276") (name "unconnected-(U$2-PadB22)") (class "Default")
      (node (ref "U$2") (pin "B22") (pinfunction "B22_B22") (pintype "bidirectional"))
    )
    (net (code "277") (name "unconnected-(U$2-PadC1)") (class "Default")
      (node (ref "U$2") (pin "C1") (pinfunction "C1_C1") (pintype "bidirectional"))
    )
    (net (code "278") (name "unconnected-(U$2-PadC5)") (class "Default")
      (node (ref "U$2") (pin "C5") (pinfunction "C5_C5") (pintype "bidirectional"))
    )
    (net (code "279") (name "unconnected-(U$2-PadC15)") (class "Default")
      (node (ref "U$2") (pin "C15") (pinfunction "C15_C15") (pintype "bidirectional"))
    )
    (net (code "280") (name "unconnected-(U$2-PadC16)") (class "Default")
      (node (ref "U$2") (pin "C16") (pinfunction "C16_C16") (pintype "bidirectional"))
    )
    (net (code "281") (name "unconnected-(U$2-PadC18)") (class "Default")
      (node (ref "U$2") (pin "C18") (pinfunction "C18_C18") (pintype "bidirectional"))
    )
    (net (code "282") (name "unconnected-(U$2-PadC19)") (class "Default")
      (node (ref "U$2") (pin "C19") (pinfunction "C19_C19") (pintype "bidirectional"))
    )
    (net (code "283") (name "unconnected-(U$2-PadC22)") (class "Default")
      (node (ref "U$2") (pin "C22") (pinfunction "C22_C22") (pintype "bidirectional"))
    )
    (net (code "284") (name "unconnected-(U$2-PadD2)") (class "Default")
      (node (ref "U$2") (pin "D2") (pinfunction "D2_D2") (pintype "bidirectional"))
    )
    (net (code "285") (name "unconnected-(U$2-PadD12)") (class "Default")
      (node (ref "U$2") (pin "D12") (pinfunction "D12_D12") (pintype "bidirectional"))
    )
    (net (code "286") (name "unconnected-(U$2-PadD13)") (class "Default")
      (node (ref "U$2") (pin "D13") (pinfunction "D13_D13") (pintype "bidirectional"))
    )
    (net (code "287") (name "unconnected-(U$2-PadE1)") (class "Default")
      (node (ref "U$2") (pin "E1") (pinfunction "E1_E1") (pintype "bidirectional"))
    )
    (net (code "288") (name "unconnected-(U$2-PadE2)") (class "Default")
      (node (ref "U$2") (pin "E2") (pinfunction "E2_E2") (pintype "bidirectional"))
    )
    (net (code "289") (name "unconnected-(U$2-PadE3)") (class "Default")
      (node (ref "U$2") (pin "E3") (pinfunction "E3_E3") (pintype "bidirectional"))
    )
    (net (code "290") (name "unconnected-(U$2-PadE5)") (class "Default")
      (node (ref "U$2") (pin "E5") (pinfunction "E5_E5") (pintype "bidirectional"))
    )
    (net (code "291") (name "unconnected-(U$2-PadE6)") (class "Default")
      (node (ref "U$2") (pin "E6") (pinfunction "E6_E6") (pintype "bidirectional"))
    )
    (net (code "292") (name "unconnected-(U$2-PadE7)") (class "Default")
      (node (ref "U$2") (pin "E7") (pinfunction "E7_E7") (pintype "bidirectional"))
    )
    (net (code "293") (name "unconnected-(U$2-PadE8)") (class "Default")
      (node (ref "U$2") (pin "E8") (pinfunction "E8_E8") (pintype "bidirectional"))
    )
    (net (code "294") (name "unconnected-(U$2-PadE9)") (class "Default")
      (node (ref "U$2") (pin "E9") (pinfunction "E9_E9") (pintype "bidirectional"))
    )
    (net (code "295") (name "unconnected-(U$2-PadE10)") (class "Default")
      (node (ref "U$2") (pin "E10") (pinfunction "E10_E10") (pintype "bidirectional"))
    )
    (net (code "296") (name "unconnected-(U$2-PadE11)") (class "Default")
      (node (ref "U$2") (pin "E11") (pinfunction "E11_E11") (pintype "bidirectional"))
    )
    (net (code "297") (name "unconnected-(U$2-PadE12)") (class "Default")
      (node (ref "U$2") (pin "E12") (pinfunction "E12_E12") (pintype "bidirectional"))
    )
    (net (code "298") (name "unconnected-(U$2-PadE13)") (class "Default")
      (node (ref "U$2") (pin "E13") (pinfunction "E13_E13") (pintype "bidirectional"))
    )
    (net (code "299") (name "unconnected-(U$2-PadE14)") (class "Default")
      (node (ref "U$2") (pin "E14") (pinfunction "E14_E14") (pintype "bidirectional"))
    )
    (net (code "300") (name "unconnected-(U$2-PadE15)") (class "Default")
      (node (ref "U$2") (pin "E15") (pinfunction "E15_E15") (pintype "bidirectional"))
    )
    (net (code "301") (name "unconnected-(U$2-PadE16)") (class "Default")
      (node (ref "U$2") (pin "E16") (pinfunction "E16_E16") (pintype "bidirectional"))
    )
    (net (code "302") (name "unconnected-(U$2-PadE17)") (class "Default")
      (node (ref "U$2") (pin "E17") (pinfunction "E17_E17") (pintype "bidirectional"))
    )
    (net (code "303") (name "unconnected-(U$2-PadE18)") (class "Default")
      (node (ref "U$2") (pin "E18") (pinfunction "E18_E18") (pintype "bidirectional"))
    )
    (net (code "304") (name "unconnected-(U$2-PadE21)") (class "Default")
      (node (ref "U$2") (pin "E21") (pinfunction "E21_E21") (pintype "bidirectional"))
    )
    (net (code "305") (name "unconnected-(U$2-PadF1)") (class "Default")
      (node (ref "U$2") (pin "F1") (pinfunction "F1_F1") (pintype "bidirectional"))
    )
    (net (code "306") (name "unconnected-(U$2-PadF2)") (class "Default")
      (node (ref "U$2") (pin "F2") (pinfunction "F2_F2") (pintype "bidirectional"))
    )
    (net (code "307") (name "unconnected-(U$2-PadF5)") (class "Default")
      (node (ref "U$2") (pin "F5") (pinfunction "F5_F5") (pintype "bidirectional"))
    )
    (net (code "308") (name "unconnected-(U$2-PadF6)") (class "Default")
      (node (ref "U$2") (pin "F6") (pinfunction "F6_F6") (pintype "bidirectional"))
    )
    (net (code "309") (name "unconnected-(U$2-PadF7)") (class "Default")
      (node (ref "U$2") (pin "F7") (pinfunction "F7_F7") (pintype "bidirectional"))
    )
    (net (code "310") (name "unconnected-(U$2-PadF8)") (class "Default")
      (node (ref "U$2") (pin "F8") (pinfunction "F8_F8") (pintype "bidirectional"))
    )
    (net (code "311") (name "unconnected-(U$2-PadF9)") (class "Default")
      (node (ref "U$2") (pin "F9") (pinfunction "F9_F9") (pintype "bidirectional"))
    )
    (net (code "312") (name "unconnected-(U$2-PadF10)") (class "Default")
      (node (ref "U$2") (pin "F10") (pinfunction "F10_F10") (pintype "bidirectional"))
    )
    (net (code "313") (name "unconnected-(U$2-PadF11)") (class "Default")
      (node (ref "U$2") (pin "F11") (pinfunction "F11_F11") (pintype "bidirectional"))
    )
    (net (code "314") (name "unconnected-(U$2-PadF12)") (class "Default")
      (node (ref "U$2") (pin "F12") (pinfunction "F12_F12") (pintype "bidirectional"))
    )
    (net (code "315") (name "unconnected-(U$2-PadF13)") (class "Default")
      (node (ref "U$2") (pin "F13") (pinfunction "F13_F13") (pintype "bidirectional"))
    )
    (net (code "316") (name "unconnected-(U$2-PadF14)") (class "Default")
      (node (ref "U$2") (pin "F14") (pinfunction "F14_F14") (pintype "bidirectional"))
    )
    (net (code "317") (name "unconnected-(U$2-PadF15)") (class "Default")
      (node (ref "U$2") (pin "F15") (pinfunction "F15_F15") (pintype "bidirectional"))
    )
    (net (code "318") (name "unconnected-(U$2-PadF16)") (class "Default")
      (node (ref "U$2") (pin "F16") (pinfunction "F16_F16") (pintype "bidirectional"))
    )
    (net (code "319") (name "unconnected-(U$2-PadF17)") (class "Default")
      (node (ref "U$2") (pin "F17") (pinfunction "F17_F17") (pintype "bidirectional"))
    )
    (net (code "320") (name "unconnected-(U$2-PadF18)") (class "Default")
      (node (ref "U$2") (pin "F18") (pinfunction "F18_F18") (pintype "bidirectional"))
    )
    (net (code "321") (name "unconnected-(U$2-PadG2)") (class "Default")
      (node (ref "U$2") (pin "G2") (pinfunction "G2_G2") (pintype "bidirectional"))
    )
    (net (code "322") (name "unconnected-(U$2-PadG5)") (class "Default")
      (node (ref "U$2") (pin "G5") (pinfunction "G5_G5") (pintype "bidirectional"))
    )
    (net (code "323") (name "unconnected-(U$2-PadG6)") (class "Default")
      (node (ref "U$2") (pin "G6") (pinfunction "G6_G6") (pintype "bidirectional"))
    )
    (net (code "324") (name "unconnected-(U$2-PadG7)") (class "Default")
      (node (ref "U$2") (pin "G7") (pinfunction "G7_G7") (pintype "bidirectional"))
    )
    (net (code "325") (name "unconnected-(U$2-PadG8)") (class "Default")
      (node (ref "U$2") (pin "G8") (pinfunction "G8_G8") (pintype "bidirectional"))
    )
    (net (code "326") (name "unconnected-(U$2-PadG9)") (class "Default")
      (node (ref "U$2") (pin "G9") (pinfunction "G9_G9") (pintype "bidirectional"))
    )
    (net (code "327") (name "unconnected-(U$2-PadG10)") (class "Default")
      (node (ref "U$2") (pin "G10") (pinfunction "G10_G10") (pintype "bidirectional"))
    )
    (net (code "328") (name "unconnected-(U$2-PadG11)") (class "Default")
      (node (ref "U$2") (pin "G11") (pinfunction "G11_G11") (pintype "bidirectional"))
    )
    (net (code "329") (name "unconnected-(U$2-PadG12)") (class "Default")
      (node (ref "U$2") (pin "G12") (pinfunction "G12_G12") (pintype "bidirectional"))
    )
    (net (code "330") (name "unconnected-(U$2-PadG13)") (class "Default")
      (node (ref "U$2") (pin "G13") (pinfunction "G13_G13") (pintype "bidirectional"))
    )
    (net (code "331") (name "unconnected-(U$2-PadG14)") (class "Default")
      (node (ref "U$2") (pin "G14") (pinfunction "G14_G14") (pintype "bidirectional"))
    )
    (net (code "332") (name "unconnected-(U$2-PadG15)") (class "Default")
      (node (ref "U$2") (pin "G15") (pinfunction "G15_G15") (pintype "bidirectional"))
    )
    (net (code "333") (name "unconnected-(U$2-PadG16)") (class "Default")
      (node (ref "U$2") (pin "G16") (pinfunction "G16_G16") (pintype "bidirectional"))
    )
    (net (code "334") (name "unconnected-(U$2-PadG17)") (class "Default")
      (node (ref "U$2") (pin "G17") (pinfunction "G17_G17") (pintype "bidirectional"))
    )
    (net (code "335") (name "unconnected-(U$2-PadG18)") (class "Default")
      (node (ref "U$2") (pin "G18") (pinfunction "G18_G18") (pintype "bidirectional"))
    )
    (net (code "336") (name "unconnected-(U$2-PadH1)") (class "Default")
      (node (ref "U$2") (pin "H1") (pinfunction "H1_H1") (pintype "bidirectional"))
    )
    (net (code "337") (name "unconnected-(U$2-PadH2)") (class "Default")
      (node (ref "U$2") (pin "H2") (pinfunction "H2_H2") (pintype "bidirectional"))
    )
    (net (code "338") (name "unconnected-(U$2-PadH3)") (class "Default")
      (node (ref "U$2") (pin "H3") (pinfunction "H3_H3") (pintype "bidirectional"))
    )
    (net (code "339") (name "unconnected-(U$2-PadH5)") (class "Default")
      (node (ref "U$2") (pin "H5") (pinfunction "H5_H5") (pintype "bidirectional"))
    )
    (net (code "340") (name "unconnected-(U$2-PadH6)") (class "Default")
      (node (ref "U$2") (pin "H6") (pinfunction "H6_H6") (pintype "bidirectional"))
    )
    (net (code "341") (name "unconnected-(U$2-PadH7)") (class "Default")
      (node (ref "U$2") (pin "H7") (pinfunction "H7_H7") (pintype "bidirectional"))
    )
    (net (code "342") (name "unconnected-(U$2-PadH16)") (class "Default")
      (node (ref "U$2") (pin "H16") (pinfunction "H16_H16") (pintype "bidirectional"))
    )
    (net (code "343") (name "unconnected-(U$2-PadH17)") (class "Default")
      (node (ref "U$2") (pin "H17") (pinfunction "H17_H17") (pintype "bidirectional"))
    )
    (net (code "344") (name "unconnected-(U$2-PadH18)") (class "Default")
      (node (ref "U$2") (pin "H18") (pinfunction "H18_H18") (pintype "bidirectional"))
    )
    (net (code "345") (name "unconnected-(U$2-PadH21)") (class "Default")
      (node (ref "U$2") (pin "H21") (pinfunction "H21_H21") (pintype "bidirectional"))
    )
    (net (code "346") (name "unconnected-(U$2-PadJ1)") (class "Default")
      (node (ref "U$2") (pin "J1") (pinfunction "J1_J1") (pintype "bidirectional"))
    )
    (net (code "347") (name "unconnected-(U$2-PadJ2)") (class "Default")
      (node (ref "U$2") (pin "J2") (pinfunction "J2_J2") (pintype "bidirectional"))
    )
    (net (code "348") (name "unconnected-(U$2-PadJ3)") (class "Default")
      (node (ref "U$2") (pin "J3") (pinfunction "J3_J3") (pintype "bidirectional"))
    )
    (net (code "349") (name "unconnected-(U$2-PadJ5)") (class "Default")
      (node (ref "U$2") (pin "J5") (pinfunction "J5_J5") (pintype "bidirectional"))
    )
    (net (code "350") (name "unconnected-(U$2-PadJ6)") (class "Default")
      (node (ref "U$2") (pin "J6") (pinfunction "J6_J6") (pintype "bidirectional"))
    )
    (net (code "351") (name "unconnected-(U$2-PadJ7)") (class "Default")
      (node (ref "U$2") (pin "J7") (pinfunction "J7_J7") (pintype "bidirectional"))
    )
    (net (code "352") (name "unconnected-(U$2-PadJ16)") (class "Default")
      (node (ref "U$2") (pin "J16") (pinfunction "J16_J16") (pintype "bidirectional"))
    )
    (net (code "353") (name "unconnected-(U$2-PadJ17)") (class "Default")
      (node (ref "U$2") (pin "J17") (pinfunction "J17_J17") (pintype "bidirectional"))
    )
    (net (code "354") (name "unconnected-(U$2-PadJ18)") (class "Default")
      (node (ref "U$2") (pin "J18") (pinfunction "J18_J18") (pintype "bidirectional"))
    )
    (net (code "355") (name "unconnected-(U$2-PadJ19)") (class "Default")
      (node (ref "U$2") (pin "J19") (pinfunction "J19_J19") (pintype "bidirectional"))
    )
    (net (code "356") (name "unconnected-(U$2-PadJ20)") (class "Default")
      (node (ref "U$2") (pin "J20") (pinfunction "J20_J20") (pintype "bidirectional"))
    )
    (net (code "357") (name "unconnected-(U$2-PadJ22)") (class "Default")
      (node (ref "U$2") (pin "J22") (pinfunction "J22_J22") (pintype "bidirectional"))
    )
    (net (code "358") (name "unconnected-(U$2-PadK3)") (class "Default")
      (node (ref "U$2") (pin "K3") (pinfunction "K3_K3") (pintype "bidirectional"))
    )
    (net (code "359") (name "unconnected-(U$2-PadK5)") (class "Default")
      (node (ref "U$2") (pin "K5") (pinfunction "K5_K5") (pintype "bidirectional"))
    )
    (net (code "360") (name "unconnected-(U$2-PadK6)") (class "Default")
      (node (ref "U$2") (pin "K6") (pinfunction "K6_K6") (pintype "bidirectional"))
    )
    (net (code "361") (name "unconnected-(U$2-PadK7)") (class "Default")
      (node (ref "U$2") (pin "K7") (pinfunction "K7_K7") (pintype "bidirectional"))
    )
    (net (code "362") (name "unconnected-(U$2-PadK16)") (class "Default")
      (node (ref "U$2") (pin "K16") (pinfunction "K16_K16") (pintype "bidirectional"))
    )
    (net (code "363") (name "unconnected-(U$2-PadK17)") (class "Default")
      (node (ref "U$2") (pin "K17") (pinfunction "K17_K17") (pintype "bidirectional"))
    )
    (net (code "364") (name "unconnected-(U$2-PadK18)") (class "Default")
      (node (ref "U$2") (pin "K18") (pinfunction "K18_K18") (pintype "bidirectional"))
    )
    (net (code "365") (name "unconnected-(U$2-PadK20)") (class "Default")
      (node (ref "U$2") (pin "K20") (pinfunction "K20_K20") (pintype "bidirectional"))
    )
    (net (code "366") (name "unconnected-(U$2-PadL3)") (class "Default")
      (node (ref "U$2") (pin "L3") (pinfunction "L3_L3") (pintype "bidirectional"))
    )
    (net (code "367") (name "unconnected-(U$2-PadL5)") (class "Default")
      (node (ref "U$2") (pin "L5") (pinfunction "L5_L5") (pintype "bidirectional"))
    )
    (net (code "368") (name "unconnected-(U$2-PadL6)") (class "Default")
      (node (ref "U$2") (pin "L6") (pinfunction "L6_L6") (pintype "bidirectional"))
    )
    (net (code "369") (name "unconnected-(U$2-PadL7)") (class "Default")
      (node (ref "U$2") (pin "L7") (pinfunction "L7_L7") (pintype "bidirectional"))
    )
    (net (code "370") (name "unconnected-(U$2-PadL16)") (class "Default")
      (node (ref "U$2") (pin "L16") (pinfunction "L16_L16") (pintype "bidirectional"))
    )
    (net (code "371") (name "unconnected-(U$2-PadL17)") (class "Default")
      (node (ref "U$2") (pin "L17") (pinfunction "L17_L17") (pintype "bidirectional"))
    )
    (net (code "372") (name "unconnected-(U$2-PadL18)") (class "Default")
      (node (ref "U$2") (pin "L18") (pinfunction "L18_L18") (pintype "bidirectional"))
    )
    (net (code "373") (name "unconnected-(U$2-PadM5)") (class "Default")
      (node (ref "U$2") (pin "M5") (pinfunction "M5_M5") (pintype "bidirectional"))
    )
    (net (code "374") (name "unconnected-(U$2-PadM6)") (class "Default")
      (node (ref "U$2") (pin "M6") (pinfunction "M6_M6") (pintype "bidirectional"))
    )
    (net (code "375") (name "unconnected-(U$2-PadM7)") (class "Default")
      (node (ref "U$2") (pin "M7") (pinfunction "M7_M7") (pintype "bidirectional"))
    )
    (net (code "376") (name "unconnected-(U$2-PadM16)") (class "Default")
      (node (ref "U$2") (pin "M16") (pinfunction "M16_M16") (pintype "bidirectional"))
    )
    (net (code "377") (name "unconnected-(U$2-PadM17)") (class "Default")
      (node (ref "U$2") (pin "M17") (pinfunction "M17_M17") (pintype "bidirectional"))
    )
    (net (code "378") (name "unconnected-(U$2-PadM18)") (class "Default")
      (node (ref "U$2") (pin "M18") (pinfunction "M18_M18") (pintype "bidirectional"))
    )
    (net (code "379") (name "unconnected-(U$2-PadN5)") (class "Default")
      (node (ref "U$2") (pin "N5") (pinfunction "N5_N5") (pintype "bidirectional"))
    )
    (net (code "380") (name "unconnected-(U$2-PadN6)") (class "Default")
      (node (ref "U$2") (pin "N6") (pinfunction "N6_N6") (pintype "bidirectional"))
    )
    (net (code "381") (name "unconnected-(U$2-PadN7)") (class "Default")
      (node (ref "U$2") (pin "N7") (pinfunction "N7_N7") (pintype "bidirectional"))
    )
    (net (code "382") (name "unconnected-(U$2-PadN16)") (class "Default")
      (node (ref "U$2") (pin "N16") (pinfunction "N16_N16") (pintype "bidirectional"))
    )
    (net (code "383") (name "unconnected-(U$2-PadN17)") (class "Default")
      (node (ref "U$2") (pin "N17") (pinfunction "N17_N17") (pintype "bidirectional"))
    )
    (net (code "384") (name "unconnected-(U$2-PadN18)") (class "Default")
      (node (ref "U$2") (pin "N18") (pinfunction "N18_N18") (pintype "bidirectional"))
    )
    (net (code "385") (name "unconnected-(U$2-PadN20)") (class "Default")
      (node (ref "U$2") (pin "N20") (pinfunction "N20_N20") (pintype "bidirectional"))
    )
    (net (code "386") (name "unconnected-(U$2-PadP3)") (class "Default")
      (node (ref "U$2") (pin "P3") (pinfunction "P3_P3") (pintype "bidirectional"))
    )
    (net (code "387") (name "unconnected-(U$2-PadP4)") (class "Default")
      (node (ref "U$2") (pin "P4") (pinfunction "P4_P4") (pintype "bidirectional"))
    )
    (net (code "388") (name "unconnected-(U$2-PadP5)") (class "Default")
      (node (ref "U$2") (pin "P5") (pinfunction "P5_P5") (pintype "bidirectional"))
    )
    (net (code "389") (name "unconnected-(U$2-PadP6)") (class "Default")
      (node (ref "U$2") (pin "P6") (pinfunction "P6_P6") (pintype "bidirectional"))
    )
    (net (code "390") (name "unconnected-(U$2-PadP7)") (class "Default")
      (node (ref "U$2") (pin "P7") (pinfunction "P7_P7") (pintype "bidirectional"))
    )
    (net (code "391") (name "unconnected-(U$2-PadP16)") (class "Default")
      (node (ref "U$2") (pin "P16") (pinfunction "P16_P16") (pintype "bidirectional"))
    )
    (net (code "392") (name "unconnected-(U$2-PadP17)") (class "Default")
      (node (ref "U$2") (pin "P17") (pinfunction "P17_P17") (pintype "bidirectional"))
    )
    (net (code "393") (name "unconnected-(U$2-PadP18)") (class "Default")
      (node (ref "U$2") (pin "P18") (pinfunction "P18_P18") (pintype "bidirectional"))
    )
    (net (code "394") (name "unconnected-(U$2-PadP19)") (class "Default")
      (node (ref "U$2") (pin "P19") (pinfunction "P19_P19") (pintype "bidirectional"))
    )
    (net (code "395") (name "unconnected-(U$2-PadP20)") (class "Default")
      (node (ref "U$2") (pin "P20") (pinfunction "P20_P20") (pintype "bidirectional"))
    )
    (net (code "396") (name "unconnected-(U$2-PadP21)") (class "Default")
      (node (ref "U$2") (pin "P21") (pinfunction "P21_P21") (pintype "bidirectional"))
    )
    (net (code "397") (name "unconnected-(U$2-PadP22)") (class "Default")
      (node (ref "U$2") (pin "P22") (pinfunction "P22_P22") (pintype "bidirectional"))
    )
    (net (code "398") (name "unconnected-(U$2-PadR1)") (class "Default")
      (node (ref "U$2") (pin "R1") (pinfunction "R1_R1") (pintype "bidirectional"))
    )
    (net (code "399") (name "unconnected-(U$2-PadR5)") (class "Default")
      (node (ref "U$2") (pin "R5") (pinfunction "R5_R5") (pintype "bidirectional"))
    )
    (net (code "400") (name "unconnected-(U$2-PadR6)") (class "Default")
      (node (ref "U$2") (pin "R6") (pinfunction "R6_R6") (pintype "bidirectional"))
    )
    (net (code "401") (name "unconnected-(U$2-PadR7)") (class "Default")
      (node (ref "U$2") (pin "R7") (pinfunction "R7_R7") (pintype "bidirectional"))
    )
    (net (code "402") (name "unconnected-(U$2-PadR16)") (class "Default")
      (node (ref "U$2") (pin "R16") (pinfunction "R16_R16") (pintype "bidirectional"))
    )
    (net (code "403") (name "unconnected-(U$2-PadR17)") (class "Default")
      (node (ref "U$2") (pin "R17") (pinfunction "R17_R17") (pintype "bidirectional"))
    )
    (net (code "404") (name "unconnected-(U$2-PadR18)") (class "Default")
      (node (ref "U$2") (pin "R18") (pinfunction "R18_R18") (pintype "bidirectional"))
    )
    (net (code "405") (name "unconnected-(U$2-PadR21)") (class "Default")
      (node (ref "U$2") (pin "R21") (pinfunction "R21_R21") (pintype "bidirectional"))
    )
    (net (code "406") (name "unconnected-(U$2-PadR22)") (class "Default")
      (node (ref "U$2") (pin "R22") (pinfunction "R22_R22") (pintype "bidirectional"))
    )
    (net (code "407") (name "unconnected-(U$2-PadT5)") (class "Default")
      (node (ref "U$2") (pin "T5") (pinfunction "T5_T5") (pintype "bidirectional"))
    )
    (net (code "408") (name "unconnected-(U$2-PadT6)") (class "Default")
      (node (ref "U$2") (pin "T6") (pinfunction "T6_T6") (pintype "bidirectional"))
    )
    (net (code "409") (name "unconnected-(U$2-PadT7)") (class "Default")
      (node (ref "U$2") (pin "T7") (pinfunction "T7_T7") (pintype "bidirectional"))
    )
    (net (code "410") (name "unconnected-(U$2-PadT8)") (class "Default")
      (node (ref "U$2") (pin "T8") (pinfunction "T8_T8") (pintype "bidirectional"))
    )
    (net (code "411") (name "unconnected-(U$2-PadT9)") (class "Default")
      (node (ref "U$2") (pin "T9") (pinfunction "T9_T9") (pintype "bidirectional"))
    )
    (net (code "412") (name "unconnected-(U$2-PadT10)") (class "Default")
      (node (ref "U$2") (pin "T10") (pinfunction "T10_T10") (pintype "bidirectional"))
    )
    (net (code "413") (name "unconnected-(U$2-PadT11)") (class "Default")
      (node (ref "U$2") (pin "T11") (pinfunction "T11_T11") (pintype "bidirectional"))
    )
    (net (code "414") (name "unconnected-(U$2-PadT12)") (class "Default")
      (node (ref "U$2") (pin "T12") (pinfunction "T12_T12") (pintype "bidirectional"))
    )
    (net (code "415") (name "unconnected-(U$2-PadT13)") (class "Default")
      (node (ref "U$2") (pin "T13") (pinfunction "T13_T13") (pintype "bidirectional"))
    )
    (net (code "416") (name "unconnected-(U$2-PadT14)") (class "Default")
      (node (ref "U$2") (pin "T14") (pinfunction "T14_T14") (pintype "bidirectional"))
    )
    (net (code "417") (name "unconnected-(U$2-PadT15)") (class "Default")
      (node (ref "U$2") (pin "T15") (pinfunction "T15_T15") (pintype "bidirectional"))
    )
    (net (code "418") (name "unconnected-(U$2-PadT16)") (class "Default")
      (node (ref "U$2") (pin "T16") (pinfunction "T16_T16") (pintype "bidirectional"))
    )
    (net (code "419") (name "unconnected-(U$2-PadT17)") (class "Default")
      (node (ref "U$2") (pin "T17") (pinfunction "T17_T17") (pintype "bidirectional"))
    )
    (net (code "420") (name "unconnected-(U$2-PadT18)") (class "Default")
      (node (ref "U$2") (pin "T18") (pinfunction "T18_T18") (pintype "bidirectional"))
    )
    (net (code "421") (name "unconnected-(U$2-PadT20)") (class "Default")
      (node (ref "U$2") (pin "T20") (pinfunction "T20_T20") (pintype "bidirectional"))
    )
    (net (code "422") (name "unconnected-(U$2-PadT21)") (class "Default")
      (node (ref "U$2") (pin "T21") (pinfunction "T21_T21") (pintype "bidirectional"))
    )
    (net (code "423") (name "unconnected-(U$2-PadU5)") (class "Default")
      (node (ref "U$2") (pin "U5") (pinfunction "U5_U5") (pintype "bidirectional"))
    )
    (net (code "424") (name "unconnected-(U$2-PadU6)") (class "Default")
      (node (ref "U$2") (pin "U6") (pinfunction "U6_U6") (pintype "bidirectional"))
    )
    (net (code "425") (name "unconnected-(U$2-PadU7)") (class "Default")
      (node (ref "U$2") (pin "U7") (pinfunction "U7_U7") (pintype "bidirectional"))
    )
    (net (code "426") (name "unconnected-(U$2-PadU8)") (class "Default")
      (node (ref "U$2") (pin "U8") (pinfunction "U8_U8") (pintype "bidirectional"))
    )
    (net (code "427") (name "unconnected-(U$2-PadU9)") (class "Default")
      (node (ref "U$2") (pin "U9") (pinfunction "U9_U9") (pintype "bidirectional"))
    )
    (net (code "428") (name "unconnected-(U$2-PadU10)") (class "Default")
      (node (ref "U$2") (pin "U10") (pinfunction "U10_U10") (pintype "bidirectional"))
    )
    (net (code "429") (name "unconnected-(U$2-PadU11)") (class "Default")
      (node (ref "U$2") (pin "U11") (pinfunction "U11_U11") (pintype "bidirectional"))
    )
    (net (code "430") (name "unconnected-(U$2-PadU12)") (class "Default")
      (node (ref "U$2") (pin "U12") (pinfunction "U12_U12") (pintype "bidirectional"))
    )
    (net (code "431") (name "unconnected-(U$2-PadU13)") (class "Default")
      (node (ref "U$2") (pin "U13") (pinfunction "U13_U13") (pintype "bidirectional"))
    )
    (net (code "432") (name "unconnected-(U$2-PadU14)") (class "Default")
      (node (ref "U$2") (pin "U14") (pinfunction "U14_U14") (pintype "bidirectional"))
    )
    (net (code "433") (name "unconnected-(U$2-PadU15)") (class "Default")
      (node (ref "U$2") (pin "U15") (pinfunction "U15_U15") (pintype "bidirectional"))
    )
    (net (code "434") (name "unconnected-(U$2-PadU16)") (class "Default")
      (node (ref "U$2") (pin "U16") (pinfunction "U16_U16") (pintype "bidirectional"))
    )
    (net (code "435") (name "unconnected-(U$2-PadU17)") (class "Default")
      (node (ref "U$2") (pin "U17") (pinfunction "U17_U17") (pintype "bidirectional"))
    )
    (net (code "436") (name "unconnected-(U$2-PadU18)") (class "Default")
      (node (ref "U$2") (pin "U18") (pinfunction "U18_U18") (pintype "bidirectional"))
    )
    (net (code "437") (name "unconnected-(U$2-PadU22)") (class "Default")
      (node (ref "U$2") (pin "U22") (pinfunction "U22_U22") (pintype "bidirectional"))
    )
    (net (code "438") (name "unconnected-(U$2-PadV5)") (class "Default")
      (node (ref "U$2") (pin "V5") (pinfunction "V5_V5") (pintype "bidirectional"))
    )
    (net (code "439") (name "unconnected-(U$2-PadV6)") (class "Default")
      (node (ref "U$2") (pin "V6") (pinfunction "V6_V6") (pintype "bidirectional"))
    )
    (net (code "440") (name "unconnected-(U$2-PadV7)") (class "Default")
      (node (ref "U$2") (pin "V7") (pinfunction "V7_V7") (pintype "bidirectional"))
    )
    (net (code "441") (name "unconnected-(U$2-PadV8)") (class "Default")
      (node (ref "U$2") (pin "V8") (pinfunction "V8_V8") (pintype "bidirectional"))
    )
    (net (code "442") (name "unconnected-(U$2-PadV9)") (class "Default")
      (node (ref "U$2") (pin "V9") (pinfunction "V9_V9") (pintype "bidirectional"))
    )
    (net (code "443") (name "unconnected-(U$2-PadV10)") (class "Default")
      (node (ref "U$2") (pin "V10") (pinfunction "V10_V10") (pintype "bidirectional"))
    )
    (net (code "444") (name "unconnected-(U$2-PadV11)") (class "Default")
      (node (ref "U$2") (pin "V11") (pinfunction "V11_V11") (pintype "bidirectional"))
    )
    (net (code "445") (name "unconnected-(U$2-PadV12)") (class "Default")
      (node (ref "U$2") (pin "V12") (pinfunction "V12_V12") (pintype "bidirectional"))
    )
    (net (code "446") (name "unconnected-(U$2-PadV13)") (class "Default")
      (node (ref "U$2") (pin "V13") (pinfunction "V13_V13") (pintype "bidirectional"))
    )
    (net (code "447") (name "unconnected-(U$2-PadV14)") (class "Default")
      (node (ref "U$2") (pin "V14") (pinfunction "V14_V14") (pintype "bidirectional"))
    )
    (net (code "448") (name "unconnected-(U$2-PadV15)") (class "Default")
      (node (ref "U$2") (pin "V15") (pinfunction "V15_V15") (pintype "bidirectional"))
    )
    (net (code "449") (name "unconnected-(U$2-PadV16)") (class "Default")
      (node (ref "U$2") (pin "V16") (pinfunction "V16_V16") (pintype "bidirectional"))
    )
    (net (code "450") (name "unconnected-(U$2-PadV17)") (class "Default")
      (node (ref "U$2") (pin "V17") (pinfunction "V17_V17") (pintype "bidirectional"))
    )
    (net (code "451") (name "unconnected-(U$2-PadV18)") (class "Default")
      (node (ref "U$2") (pin "V18") (pinfunction "V18_V18") (pintype "bidirectional"))
    )
    (net (code "452") (name "unconnected-(U$2-PadV20)") (class "Default")
      (node (ref "U$2") (pin "V20") (pinfunction "V20_V20") (pintype "bidirectional"))
    )
    (net (code "453") (name "unconnected-(U$2-PadW3)") (class "Default")
      (node (ref "U$2") (pin "W3") (pinfunction "W3_W3") (pintype "bidirectional"))
    )
    (net (code "454") (name "unconnected-(U$2-PadW9)") (class "Default")
      (node (ref "U$2") (pin "W9") (pinfunction "W9_W9") (pintype "bidirectional"))
    )
    (net (code "455") (name "unconnected-(U$2-PadW11)") (class "Default")
      (node (ref "U$2") (pin "W11") (pinfunction "W11_W11") (pintype "bidirectional"))
    )
    (net (code "456") (name "unconnected-(U$2-PadW12)") (class "Default")
      (node (ref "U$2") (pin "W12") (pinfunction "W12_W12") (pintype "bidirectional"))
    )
    (net (code "457") (name "unconnected-(U$2-PadW14)") (class "Default")
      (node (ref "U$2") (pin "W14") (pinfunction "W14_W14") (pintype "bidirectional"))
    )
    (net (code "458") (name "unconnected-(U$2-PadW20)") (class "Default")
      (node (ref "U$2") (pin "W20") (pinfunction "W20_W20") (pintype "bidirectional"))
    )
    (net (code "459") (name "unconnected-(U$2-PadW21)") (class "Default")
      (node (ref "U$2") (pin "W21") (pinfunction "W21_W21") (pintype "bidirectional"))
    )
    (net (code "460") (name "unconnected-(U$2-X1-PadY1)") (class "Default")
      (node (ref "U$2") (pin "Y1") (pinfunction "X1_Y1") (pintype "bidirectional"))
    )
    (net (code "461") (name "unconnected-(U$2-X4-PadY4)") (class "Default")
      (node (ref "U$2") (pin "Y4") (pinfunction "X4_Y4") (pintype "bidirectional"))
    )
    (net (code "462") (name "unconnected-(U$2-X5-PadY5)") (class "Default")
      (node (ref "U$2") (pin "Y5") (pinfunction "X5_Y5") (pintype "bidirectional"))
    )
    (net (code "463") (name "unconnected-(U$2-X7-PadY7)") (class "Default")
      (node (ref "U$2") (pin "Y7") (pinfunction "X7_Y7") (pintype "bidirectional"))
    )
    (net (code "464") (name "unconnected-(U$2-X8-PadY8)") (class "Default")
      (node (ref "U$2") (pin "Y8") (pinfunction "X8_Y8") (pintype "bidirectional"))
    )
    (net (code "465") (name "unconnected-(U$2-X9-PadY9)") (class "Default")
      (node (ref "U$2") (pin "Y9") (pinfunction "X9_Y9") (pintype "bidirectional"))
    )
    (net (code "466") (name "unconnected-(U$2-X11-PadY11)") (class "Default")
      (node (ref "U$2") (pin "Y11") (pinfunction "X11_Y11") (pintype "bidirectional"))
    )
    (net (code "467") (name "unconnected-(U$2-X12-PadY12)") (class "Default")
      (node (ref "U$2") (pin "Y12") (pinfunction "X12_Y12") (pintype "bidirectional"))
    )
    (net (code "468") (name "unconnected-(U$2-X15-PadY15)") (class "Default")
      (node (ref "U$2") (pin "Y15") (pinfunction "X15_Y15") (pintype "bidirectional"))
    )
    (net (code "469") (name "unconnected-(U$2-X19-PadY19)") (class "Default")
      (node (ref "U$2") (pin "Y19") (pinfunction "X19_Y19") (pintype "bidirectional"))
    )
    (net (code "470") (name "unconnected-(U$2-X21-PadY21)") (class "Default")
      (node (ref "U$2") (pin "Y21") (pinfunction "X21_Y21") (pintype "bidirectional"))
    )
    (net (code "471") (name "unconnected-(U$2-X22-PadY22)") (class "Default")
      (node (ref "U$2") (pin "Y22") (pinfunction "X22_Y22") (pintype "bidirectional"))
    )
    (net (code "472") (name "unconnected-(U$2-Y4-PadAA4)") (class "Default")
      (node (ref "U$2") (pin "AA4") (pinfunction "Y4_AA4") (pintype "bidirectional"))
    )
    (net (code "473") (name "unconnected-(U$2-Y5-PadAA5)") (class "Default")
      (node (ref "U$2") (pin "AA5") (pinfunction "Y5_AA5") (pintype "bidirectional"))
    )
    (net (code "474") (name "unconnected-(U$2-Y6-PadAA6)") (class "Default")
      (node (ref "U$2") (pin "AA6") (pinfunction "Y6_AA6") (pintype "bidirectional"))
    )
    (net (code "475") (name "unconnected-(U$2-Y7-PadAA7)") (class "Default")
      (node (ref "U$2") (pin "AA7") (pinfunction "Y7_AA7") (pintype "bidirectional"))
    )
    (net (code "476") (name "unconnected-(U$2-Y8-PadAA8)") (class "Default")
      (node (ref "U$2") (pin "AA8") (pinfunction "Y8_AA8") (pintype "bidirectional"))
    )
    (net (code "477") (name "unconnected-(U$2-Y11-PadAA11)") (class "Default")
      (node (ref "U$2") (pin "AA11") (pinfunction "Y11_AA11") (pintype "bidirectional"))
    )
    (net (code "478") (name "unconnected-(U$2-Y12-PadAA12)") (class "Default")
      (node (ref "U$2") (pin "AA12") (pinfunction "Y12_AA12") (pintype "bidirectional"))
    )
    (net (code "479") (name "unconnected-(U$2-Y15-PadAA15)") (class "Default")
      (node (ref "U$2") (pin "AA15") (pinfunction "Y15_AA15") (pintype "bidirectional"))
    )
    (net (code "480") (name "unconnected-(U$2-Z2-PadAB2)") (class "Default")
      (node (ref "U$2") (pin "AB2") (pinfunction "Z2_AB2") (pintype "bidirectional"))
    )
    (net (code "481") (name "unconnected-(U$2-Z3-PadAB3)") (class "Default")
      (node (ref "U$2") (pin "AB3") (pinfunction "Z3_AB3") (pintype "bidirectional"))
    )
    (net (code "482") (name "unconnected-(U$2-Z6-PadAB6)") (class "Default")
      (node (ref "U$2") (pin "AB6") (pinfunction "Z6_AB6") (pintype "bidirectional"))
    )
    (net (code "483") (name "unconnected-(U$2-Z8-PadAB8)") (class "Default")
      (node (ref "U$2") (pin "AB8") (pinfunction "Z8_AB8") (pintype "bidirectional"))
    )
    (net (code "484") (name "unconnected-(U$2-Z9-PadAB9)") (class "Default")
      (node (ref "U$2") (pin "AB9") (pinfunction "Z9_AB9") (pintype "bidirectional"))
    )
    (net (code "485") (name "unconnected-(U$2-Z11-PadAB11)") (class "Default")
      (node (ref "U$2") (pin "AB11") (pinfunction "Z11_AB11") (pintype "bidirectional"))
    )
    (net (code "486") (name "unconnected-(U$2-Z12-PadAB12)") (class "Default")
      (node (ref "U$2") (pin "AB12") (pinfunction "Z12_AB12") (pintype "bidirectional"))
    )
    (net (code "487") (name "unconnected-(U$2-Z15-PadAB15)") (class "Default")
      (node (ref "U$2") (pin "AB15") (pinfunction "Z15_AB15") (pintype "bidirectional"))
    )
    (net (code "488") (name "unconnected-(U$2-Z20-PadAB20)") (class "Default")
      (node (ref "U$2") (pin "AB20") (pinfunction "Z20_AB20") (pintype "bidirectional"))
    )
    (net (code "489") (name "unconnected-(U$2-Z21-PadAB21)") (class "Default")
      (node (ref "U$2") (pin "AB21") (pinfunction "Z21_AB21") (pintype "bidirectional"))
    )
  )
)
